# ngv-main.net
KiCad netlist of a schematic drawn in Altium Designer
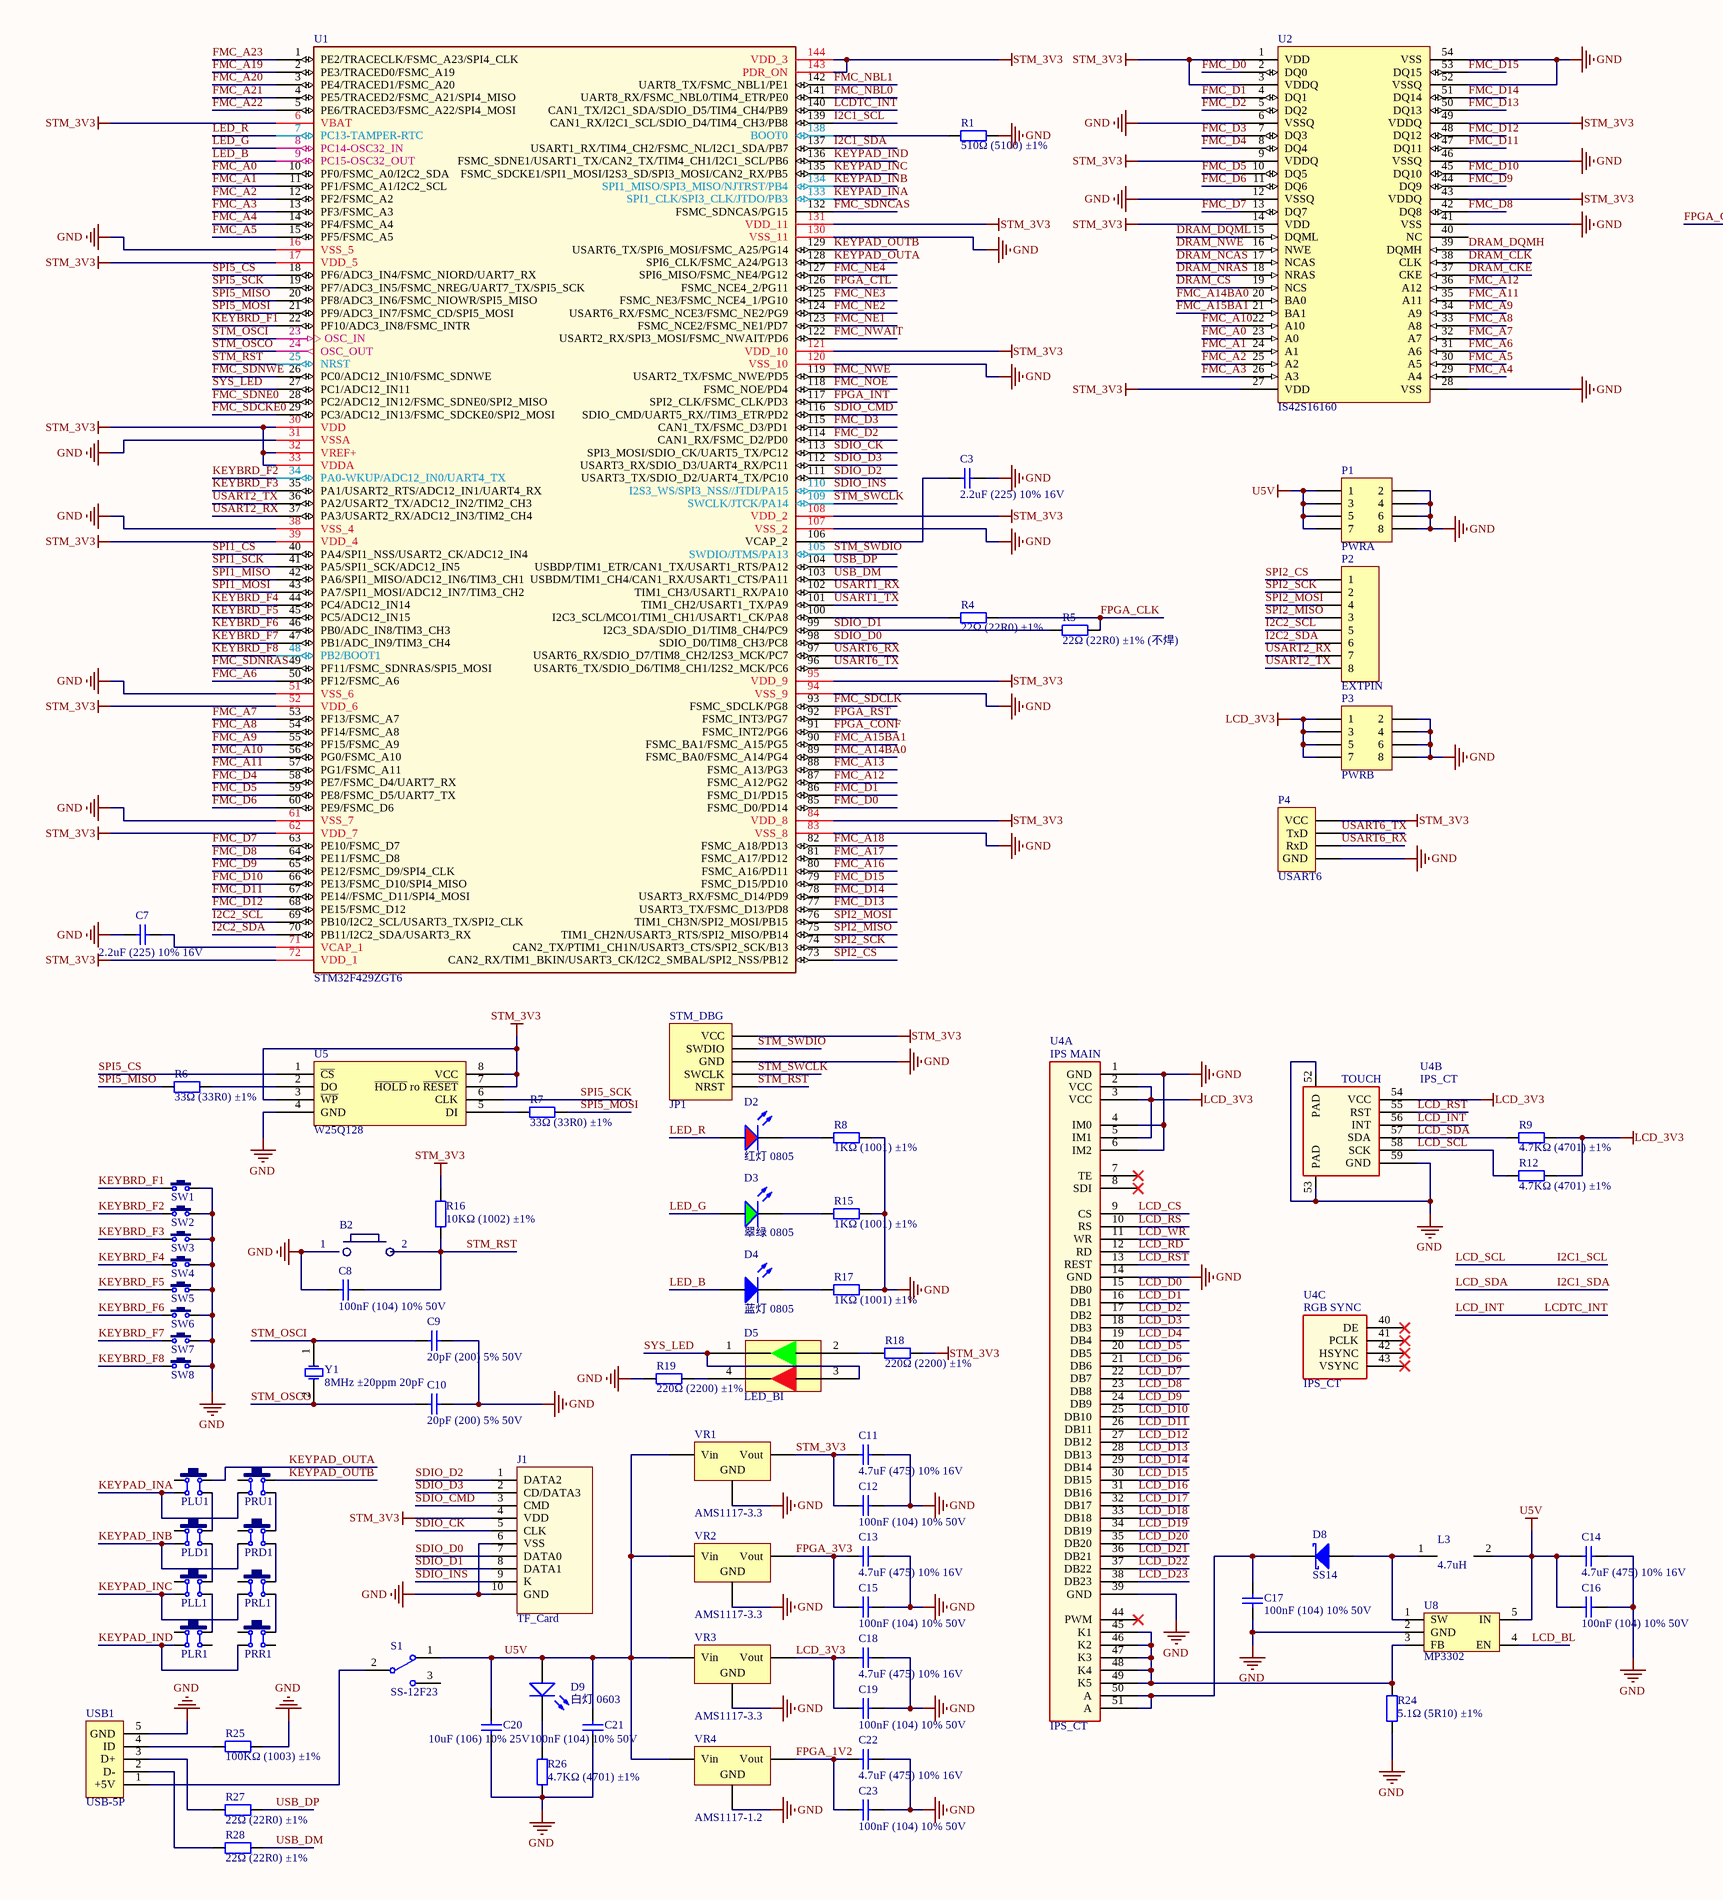
[diagram p0: ngv-main.SchDoc, left]
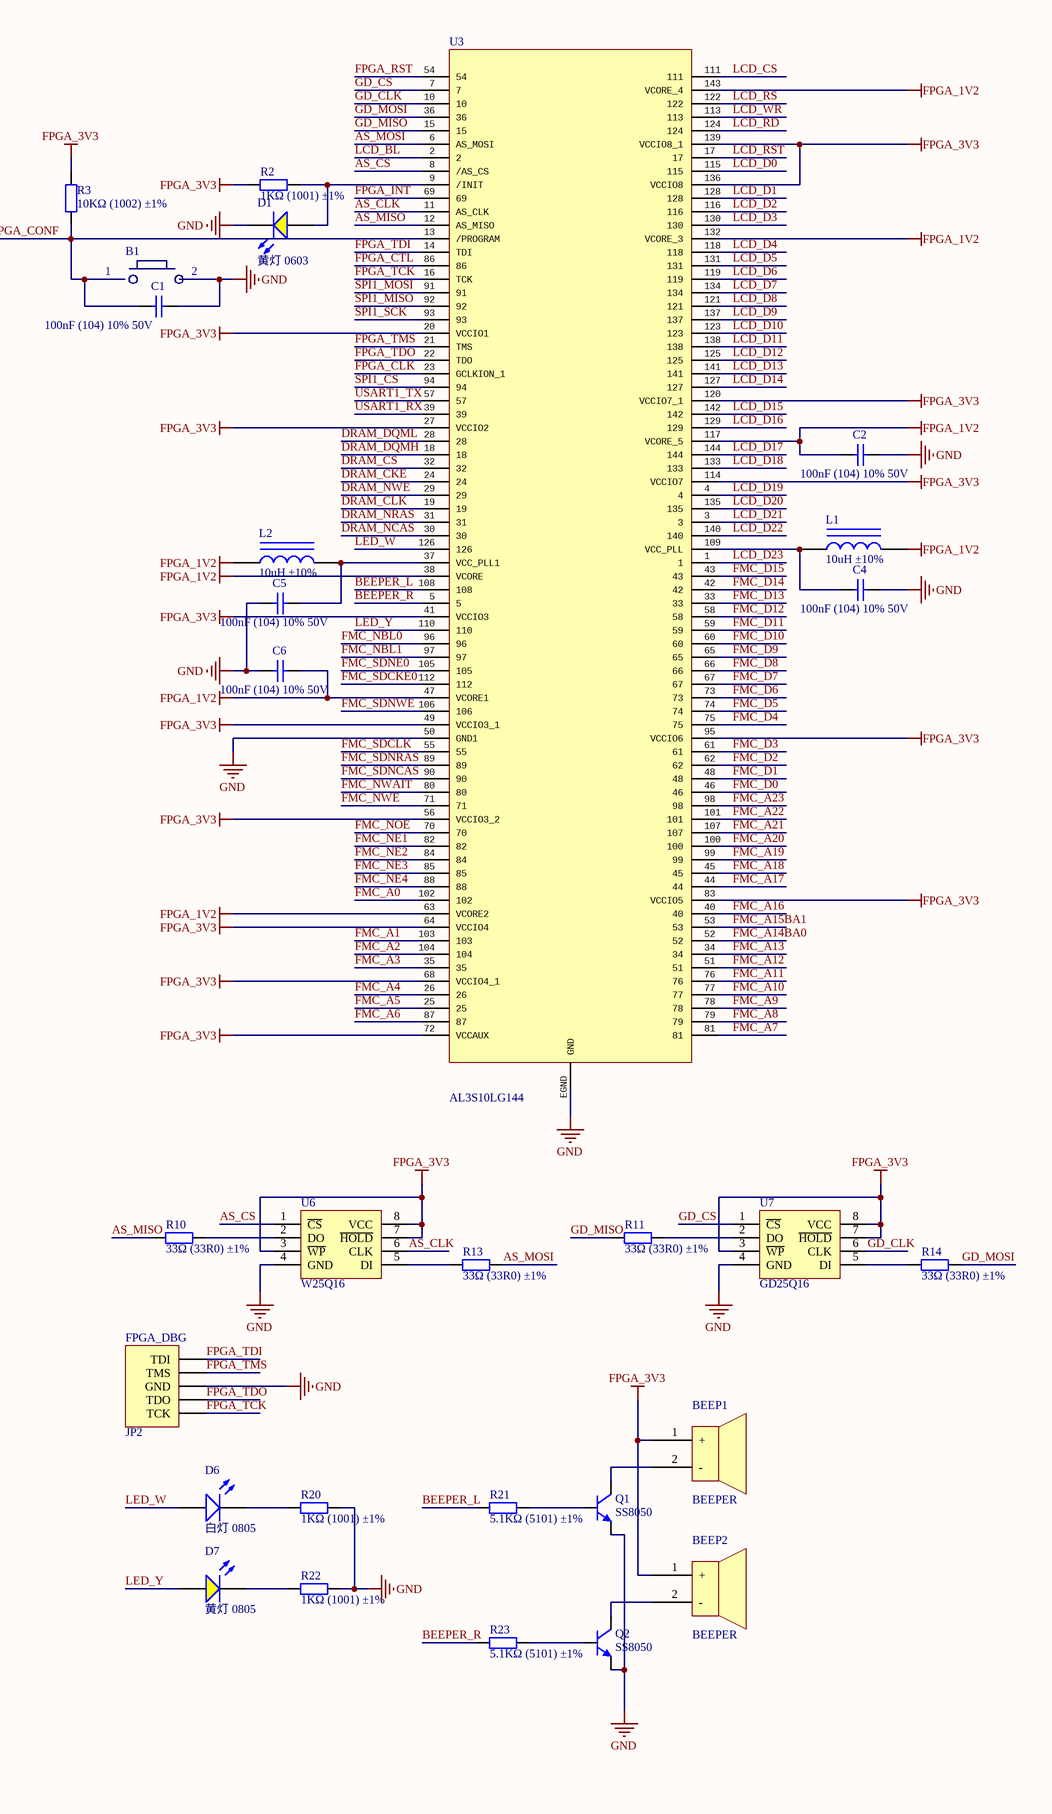
[diagram p1: ngv-main.SchDoc, right]

(export (version "E")
  (design (tool "Eeschema 10.0.6"))
  (components
    (comp (ref "B1")
      (value "B1")
      (footprint "MetalButton")
      (libsource (lib "MetalButton") (part "MetalButton"))
    )
    (comp (ref "B2")
      (value "B1")
      (footprint "MetalButton")
      (libsource (lib "MetalButton") (part "MetalButton"))
    )
    (comp (ref "BEEP1") (value "BEEPER") (footprint "BEEPER") (libsource (lib "ngv-main") (part "BEEPER")))
    (comp (ref "BEEP2") (value "BEEPER") (footprint "BEEPER") (libsource (lib "ngv-main") (part "BEEPER")))
    (comp (ref "C1")
      (value "100nF (104) 10% 50V")
      (footprint "0603_C")
      (description "贴片电容")
      (libsource (lib "Miscellaneous Devices LC") (part "0603 100nF (104) 10% 50V"))
    )
    (comp (ref "C2")
      (value "100nF (104) 10% 50V")
      (footprint "0603_C")
      (description "贴片电容")
      (libsource (lib "Miscellaneous Devices LC") (part "0603 100nF (104) 10% 50V"))
    )
    (comp (ref "C3")
      (value "2.2uF (225) 10% 16V")
      (footprint "0603_C")
      (description "贴片电容")
      (libsource (lib "Miscellaneous Devices LC") (part "0603 2.2uF (225) 10% 16V"))
    )
    (comp (ref "C4")
      (value "100nF (104) 10% 50V")
      (footprint "0603_C")
      (description "贴片电容")
      (libsource (lib "Miscellaneous Devices LC") (part "0603 100nF (104) 10% 50V"))
    )
    (comp (ref "C5")
      (value "100nF (104) 10% 50V")
      (footprint "0603_C")
      (description "贴片电容")
      (libsource (lib "Miscellaneous Devices LC") (part "0603 100nF (104) 10% 50V"))
    )
    (comp (ref "C6")
      (value "100nF (104) 10% 50V")
      (footprint "0603_C")
      (description "贴片电容")
      (libsource (lib "Miscellaneous Devices LC") (part "0603 100nF (104) 10% 50V"))
    )
    (comp (ref "C7")
      (value "2.2uF (225) 10% 16V")
      (footprint "0603_C")
      (description "贴片电容")
      (libsource (lib "Miscellaneous Devices LC") (part "0603 2.2uF (225) 10% 16V"))
    )
    (comp (ref "C8")
      (value "100nF (104) 10% 50V")
      (footprint "0603_C")
      (description "贴片电容")
      (libsource (lib "Miscellaneous Devices LC") (part "0603 100nF (104) 10% 50V"))
    )
    (comp (ref "C9")
      (value "20pF (200) 5% 50V")
      (footprint "0603_C")
      (description "贴片电容")
      (libsource (lib "Miscellaneous Devices LC") (part "0603 20pF (200) 5% 50V"))
    )
    (comp (ref "C10")
      (value "20pF (200) 5% 50V")
      (footprint "0603_C")
      (description "贴片电容")
      (libsource (lib "Miscellaneous Devices LC") (part "0603 20pF (200) 5% 50V"))
    )
    (comp (ref "C11")
      (value "4.7uF (475) 10% 16V")
      (footprint "0603_C")
      (description "贴片电容")
      (libsource (lib "Miscellaneous Devices LC") (part "0603 4.7uF (475) 10% 16V"))
    )
    (comp (ref "C12")
      (value "100nF (104) 10% 50V")
      (footprint "0603_C")
      (description "贴片电容")
      (libsource (lib "Miscellaneous Devices LC") (part "0603 100nF (104) 10% 50V"))
    )
    (comp (ref "C13")
      (value "4.7uF (475) 10% 16V")
      (footprint "0603_C")
      (description "贴片电容")
      (libsource (lib "Miscellaneous Devices LC") (part "0603 4.7uF (475) 10% 16V"))
    )
    (comp (ref "C14")
      (value "4.7uF (475) 10% 16V")
      (footprint "0603_C")
      (description "贴片电容")
      (libsource (lib "Miscellaneous Devices LC") (part "0603 4.7uF (475) 10% 16V"))
    )
    (comp (ref "C15")
      (value "100nF (104) 10% 50V")
      (footprint "0603_C")
      (description "贴片电容")
      (libsource (lib "Miscellaneous Devices LC") (part "0603 100nF (104) 10% 50V"))
    )
    (comp (ref "C16")
      (value "100nF (104) 10% 50V")
      (footprint "0603_C")
      (description "贴片电容")
      (libsource (lib "Miscellaneous Devices LC") (part "0603 100nF (104) 10% 50V"))
    )
    (comp (ref "C17")
      (value "100nF (104) 10% 50V")
      (footprint "0603_C")
      (description "贴片电容")
      (libsource (lib "Miscellaneous Devices LC") (part "0603 100nF (104) 10% 50V"))
    )
    (comp (ref "C18")
      (value "4.7uF (475) 10% 16V")
      (footprint "0603_C")
      (description "贴片电容")
      (libsource (lib "Miscellaneous Devices LC") (part "0603 4.7uF (475) 10% 16V"))
    )
    (comp (ref "C19")
      (value "100nF (104) 10% 50V")
      (footprint "0603_C")
      (description "贴片电容")
      (libsource (lib "Miscellaneous Devices LC") (part "0603 100nF (104) 10% 50V"))
    )
    (comp (ref "C20")
      (value "10uF (106) 10% 25V")
      (footprint "0805_C")
      (description "贴片电容")
      (libsource (lib "Miscellaneous Devices LC") (part "0805 10uF (106) 10% 25V"))
    )
    (comp (ref "C21")
      (value "100nF (104) 10% 50V")
      (footprint "0603_C")
      (description "贴片电容")
      (libsource (lib "Miscellaneous Devices LC") (part "0603 100nF (104) 10% 50V"))
    )
    (comp (ref "C22")
      (value "4.7uF (475) 10% 16V")
      (footprint "0603_C")
      (description "贴片电容")
      (libsource (lib "Miscellaneous Devices LC") (part "0603 4.7uF (475) 10% 16V"))
    )
    (comp (ref "C23")
      (value "100nF (104) 10% 50V")
      (footprint "0603_C")
      (description "贴片电容")
      (libsource (lib "Miscellaneous Devices LC") (part "0603 100nF (104) 10% 50V"))
    )
    (comp (ref "D1")
      (value "黄灯 0603")
      (footprint "0603_LED_S1")
      (description "发光二极管")
      (libsource (lib "Miscellaneous Devices LC") (part "0603 黄灯"))
    )
    (comp (ref "D2")
      (value "红灯 0805")
      (footprint "0805_LED_S1")
      (description "发光二极管")
      (libsource (lib "Miscellaneous Devices LC") (part "0805 红灯"))
    )
    (comp (ref "D3")
      (value "翠绿 0805")
      (footprint "0805_LED_S1")
      (description "发光二极管")
      (libsource (lib "Miscellaneous Devices LC") (part "0805 翠绿"))
    )
    (comp (ref "D4")
      (value "蓝灯 0805")
      (footprint "0805_LED_S1")
      (description "发光二极管")
      (libsource (lib "Miscellaneous Devices LC") (part "0805 蓝灯"))
    )
    (comp (ref "D5") (value "LED_BI") (footprint "LED_BI") (libsource (lib "ngv-main") (part "LED_BI")))
    (comp (ref "D6")
      (value "白灯 0805")
      (footprint "0805_LED_S1")
      (description "发光二极管")
      (libsource (lib "Miscellaneous Devices LC") (part "0805 白灯"))
    )
    (comp (ref "D7")
      (value "黄灯 0805")
      (footprint "0805_LED_S1")
      (description "发光二极管")
      (libsource (lib "Miscellaneous Devices LC") (part "0805 黄灯"))
    )
    (comp (ref "D8")
      (value "SS14")
      (footprint "SOD123")
      (fields (field (name "PUBLISHER") "Altium Limited"))
      (libsource (lib "Tiky_IPS_CT") (part "SS14"))
    )
    (comp (ref "D9")
      (value "白灯 0603")
      (footprint "0603_LED_S1")
      (description "发光二极管")
      (libsource (lib "Miscellaneous Devices LC") (part "0603 白灯"))
    )
    (comp (ref "J1")
      (value "TF_Card")
      (footprint "Micro SD")
      (description "TF卡座")
      (fields (field (name "版权归属") "源创客"))
      (libsource (lib "4.1   - 接口类") (part "TF_Card"))
    )
    (comp (ref "JP1")
      (value "STM_DBG")
      (footprint "XH2.54-WS-5P")
      (description "STM32")
      (fields (field (name "版权归属") "源创客"))
      (libsource (lib "ngv-main") (part "STM_HDR"))
    )
    (comp (ref "JP2")
      (value "FPGA_DBG")
      (footprint "XH2.54-WS-5P")
      (description "FPGA")
      (fields (field (name "版权归属") "源创客"))
      (libsource (lib "ngv-main") (part "FPGA_HDR"))
    )
    (comp (ref "L1")
      (value "10uH ±10%")
      (footprint "0603_L")
      (description "贴片电感")
      (libsource (lib "Miscellaneous Devices LC") (part "0603 10uH 10%"))
    )
    (comp (ref "L2")
      (value "10uH ±10%")
      (footprint "0603_L")
      (description "贴片电感")
      (libsource (lib "Miscellaneous Devices LC") (part "0603 10uH 10%"))
    )
    (comp (ref "L3") (value "4.7uH") (footprint "L453226") (libsource (lib "Tiky_IPS_CT") (part "4.7uH")))
    (comp (ref "P1")
      (value "PWRA")
      (footprint "HDR2X4")
      (description "Header, 4-Pin, Dual row")
      (fields (field (name "PUBLISHER") "Altium Limited"))
      (libsource (lib "Miscellaneous Connectors") (part "Header 4X2"))
    )
    (comp (ref "P2")
      (value "EXTPIN")
      (footprint "HDR1X8")
      (description "Header, 8-Pin")
      (fields (field (name "PUBLISHER") "Altium Limited"))
      (libsource (lib "Miscellaneous Connectors") (part "Header 8"))
    )
    (comp (ref "P3")
      (value "PWRB")
      (footprint "HDR2X4")
      (description "Header, 4-Pin, Dual row")
      (fields (field (name "PUBLISHER") "Altium Limited"))
      (libsource (lib "Miscellaneous Connectors") (part "Header 4X2"))
    )
    (comp (ref "P4")
      (value "USART6")
      (footprint "HDR1X4H")
      (description "Header, 4-Pin, Right Angle")
      (fields (field (name "PUBLISHER") "Altium Limited"))
      (libsource (lib "Miscellaneous Connectors") (part "Header 4H"))
    )
    (comp (ref "PLD1")
      (value "12x12x5")
      (footprint "TSW SMD-12*12*6")
      (description "贴片12x12轻触开关")
      (fields (field (name "版权归属") "源创客"))
      (libsource (lib "5.1   - 按键-开关") (part "TSW SMD-12x12"))
    )
    (comp (ref "PLL1")
      (value "12x12x5")
      (footprint "TSW SMD-12*12*6")
      (description "贴片12x12轻触开关")
      (fields (field (name "版权归属") "源创客"))
      (libsource (lib "5.1   - 按键-开关") (part "TSW SMD-12x12"))
    )
    (comp (ref "PLR1")
      (value "12x12x5")
      (footprint "TSW SMD-12*12*6")
      (description "贴片12x12轻触开关")
      (fields (field (name "版权归属") "源创客"))
      (libsource (lib "5.1   - 按键-开关") (part "TSW SMD-12x12"))
    )
    (comp (ref "PLU1")
      (value "12x12x5")
      (footprint "TSW SMD-12*12*6")
      (description "贴片12x12轻触开关")
      (fields (field (name "版权归属") "源创客"))
      (libsource (lib "5.1   - 按键-开关") (part "TSW SMD-12x12"))
    )
    (comp (ref "PRD1")
      (value "12x12x5")
      (footprint "TSW SMD-12*12*6")
      (description "贴片12x12轻触开关")
      (fields (field (name "版权归属") "源创客"))
      (libsource (lib "5.1   - 按键-开关") (part "TSW SMD-12x12"))
    )
    (comp (ref "PRL1")
      (value "12x12x5")
      (footprint "TSW SMD-12*12*6")
      (description "贴片12x12轻触开关")
      (fields (field (name "版权归属") "源创客"))
      (libsource (lib "5.1   - 按键-开关") (part "TSW SMD-12x12"))
    )
    (comp (ref "PRR1")
      (value "12x12x5")
      (footprint "TSW SMD-12*12*6")
      (description "贴片12x12轻触开关")
      (fields (field (name "版权归属") "源创客"))
      (libsource (lib "5.1   - 按键-开关") (part "TSW SMD-12x12"))
    )
    (comp (ref "PRU1")
      (value "12x12x5")
      (footprint "TSW SMD-12*12*6")
      (description "贴片12x12轻触开关")
      (fields (field (name "版权归属") "源创客"))
      (libsource (lib "5.1   - 按键-开关") (part "TSW SMD-12x12"))
    )
    (comp (ref "Q1")
      (value "SS8050")
      (footprint "SOT23-3M")
      (description "高频放大-NPN型")
      (fields (field (name "版权归属") "源创客"))
      (libsource (lib "6.2   - 三极管") (part "8050-SMD"))
    )
    (comp (ref "Q2")
      (value "SS8050")
      (footprint "SOT23-3M")
      (description "高频放大-NPN型")
      (fields (field (name "版权归属") "源创客"))
      (libsource (lib "6.2   - 三极管") (part "8050-SMD"))
    )
    (comp (ref "R1")
      (value "510Ω (5100) ±1%")
      (footprint "0603_R")
      (description "贴片电阻")
      (libsource (lib "Miscellaneous Devices LC") (part "0603 510Ω (5100) 1%"))
    )
    (comp (ref "R2")
      (value "1KΩ (1001) ±1%")
      (footprint "0603_R")
      (description "贴片电阻")
      (libsource (lib "Miscellaneous Devices LC") (part "0603 1KΩ (1001) 1%"))
    )
    (comp (ref "R3")
      (value "10KΩ (1002) ±1%")
      (footprint "0603_R")
      (description "贴片电阻")
      (libsource (lib "Miscellaneous Devices LC") (part "0603 10KΩ (1002) 1%"))
    )
    (comp (ref "R4")
      (value "22Ω (22R0) ±1%")
      (footprint "0805_R")
      (description "贴片电阻")
      (libsource (lib "Miscellaneous Devices LC") (part "0805 22Ω (22R0) 1%"))
    )
    (comp (ref "R5")
      (value "22Ω (22R0) ±1% (不焊)")
      (footprint "0805_R")
      (description "贴片电阻")
      (libsource (lib "Miscellaneous Devices LC") (part "0805 22Ω (22R0) 1%"))
    )
    (comp (ref "R6")
      (value "33Ω (33R0) ±1%")
      (footprint "0603_R")
      (description "贴片电阻")
      (libsource (lib "Miscellaneous Devices LC") (part "0603 33Ω (33R0) 1%"))
    )
    (comp (ref "R7")
      (value "33Ω (33R0) ±1%")
      (footprint "0603_R")
      (description "贴片电阻")
      (libsource (lib "Miscellaneous Devices LC") (part "0603 33Ω (33R0) 1%"))
    )
    (comp (ref "R8")
      (value "1KΩ (1001) ±1%")
      (footprint "0603_R")
      (description "贴片电阻")
      (libsource (lib "Miscellaneous Devices LC") (part "0603 1KΩ (1001) 1%"))
    )
    (comp (ref "R9")
      (value "4.7KΩ (4701) ±1%")
      (footprint "0603_R")
      (description "贴片电阻")
      (libsource (lib "Miscellaneous Devices LC") (part "0603 4.7KΩ (4701) 1%"))
    )
    (comp (ref "R10")
      (value "33Ω (33R0) ±1%")
      (footprint "0603_R")
      (description "贴片电阻")
      (libsource (lib "Miscellaneous Devices LC") (part "0603 33Ω (33R0) 1%"))
    )
    (comp (ref "R11")
      (value "33Ω (33R0) ±1%")
      (footprint "0603_R")
      (description "贴片电阻")
      (libsource (lib "Miscellaneous Devices LC") (part "0603 33Ω (33R0) 1%"))
    )
    (comp (ref "R12")
      (value "4.7KΩ (4701) ±1%")
      (footprint "0603_R")
      (description "贴片电阻")
      (libsource (lib "Miscellaneous Devices LC") (part "0603 4.7KΩ (4701) 1%"))
    )
    (comp (ref "R13")
      (value "33Ω (33R0) ±1%")
      (footprint "0603_R")
      (description "贴片电阻")
      (libsource (lib "Miscellaneous Devices LC") (part "0603 33Ω (33R0) 1%"))
    )
    (comp (ref "R14")
      (value "33Ω (33R0) ±1%")
      (footprint "0603_R")
      (description "贴片电阻")
      (libsource (lib "Miscellaneous Devices LC") (part "0603 33Ω (33R0) 1%"))
    )
    (comp (ref "R15")
      (value "1KΩ (1001) ±1%")
      (footprint "0603_R")
      (description "贴片电阻")
      (libsource (lib "Miscellaneous Devices LC") (part "0603 1KΩ (1001) 1%"))
    )
    (comp (ref "R16")
      (value "10KΩ (1002) ±1%")
      (footprint "0603_R")
      (description "贴片电阻")
      (libsource (lib "Miscellaneous Devices LC") (part "0603 10KΩ (1002) 1%"))
    )
    (comp (ref "R17")
      (value "1KΩ (1001) ±1%")
      (footprint "0603_R")
      (description "贴片电阻")
      (libsource (lib "Miscellaneous Devices LC") (part "0603 1KΩ (1001) 1%"))
    )
    (comp (ref "R18")
      (value "220Ω (2200) ±1%")
      (footprint "0402_R")
      (description "贴片电阻")
      (libsource (lib "Miscellaneous Devices LC") (part "0402 220Ω (2200) 1%"))
    )
    (comp (ref "R19")
      (value "220Ω (2200) ±1%")
      (footprint "0402_R")
      (description "贴片电阻")
      (libsource (lib "Miscellaneous Devices LC") (part "0402 220Ω (2200) 1%"))
    )
    (comp (ref "R20")
      (value "1KΩ (1001) ±1%")
      (footprint "0603_R")
      (description "贴片电阻")
      (libsource (lib "Miscellaneous Devices LC") (part "0603 1KΩ (1001) 1%"))
    )
    (comp (ref "R21")
      (value "5.1KΩ (5101) ±1%")
      (footprint "0603_R")
      (description "贴片电阻")
      (libsource (lib "Miscellaneous Devices LC") (part "0603 5.1KΩ (5101) 1%"))
    )
    (comp (ref "R22")
      (value "1KΩ (1001) ±1%")
      (footprint "0603_R")
      (description "贴片电阻")
      (libsource (lib "Miscellaneous Devices LC") (part "0603 1KΩ (1001) 1%"))
    )
    (comp (ref "R23")
      (value "5.1KΩ (5101) ±1%")
      (footprint "0603_R")
      (description "贴片电阻")
      (libsource (lib "Miscellaneous Devices LC") (part "0603 5.1KΩ (5101) 1%"))
    )
    (comp (ref "R24")
      (value "5.1Ω (5R10) ±1%")
      (footprint "0603_R")
      (description "贴片电阻")
      (libsource (lib "Miscellaneous Devices LC") (part "0603 5.1Ω (5R10) 1%"))
    )
    (comp (ref "R25")
      (value "100KΩ (1003) ±1%")
      (footprint "0603_R")
      (description "贴片电阻")
      (libsource (lib "Miscellaneous Devices LC") (part "0603 100KΩ (1003) 1%"))
    )
    (comp (ref "R26")
      (value "4.7KΩ (4701) ±1%")
      (footprint "0603_R")
      (description "贴片电阻")
      (libsource (lib "") (part "0603 4.7KΩ (4701) 1%_1"))
    )
    (comp (ref "R27")
      (value "22Ω (22R0) ±1%")
      (footprint "0603_R")
      (description "贴片电阻")
      (libsource (lib "Miscellaneous Devices LC") (part "0603 22Ω (22R0) 1%"))
    )
    (comp (ref "R28")
      (value "22Ω (22R0) ±1%")
      (footprint "0603_R")
      (description "贴片电阻")
      (libsource (lib "Miscellaneous Devices LC") (part "0603 22Ω (22R0) 1%"))
    )
    (comp (ref "S1")
      (value "SS-12F23")
      (footprint "SS-12F23")
      (description "1路波动开关")
      (fields (field (name "版权归属") "源创客"))
      (libsource (lib "5.1   - 按键-开关") (part "SSW-1P"))
    )
    (comp (ref "SW1")
      (value "3x6x5")
      (footprint "TSW SMD-3*6*4.3")
      (description "3x6轻触开关")
      (fields (field (name "版权归属") "源创客"))
      (libsource (lib "5.1   - 按键-开关") (part "TSW 3x6"))
    )
    (comp (ref "SW2")
      (value "3x6x5")
      (footprint "TSW SMD-3*6*4.3")
      (description "3x6轻触开关")
      (fields (field (name "版权归属") "源创客"))
      (libsource (lib "5.1   - 按键-开关") (part "TSW 3x6"))
    )
    (comp (ref "SW3")
      (value "3x6x5")
      (footprint "TSW SMD-3*6*4.3")
      (description "3x6轻触开关")
      (fields (field (name "版权归属") "源创客"))
      (libsource (lib "5.1   - 按键-开关") (part "TSW 3x6"))
    )
    (comp (ref "SW4")
      (value "3x6x5")
      (footprint "TSW SMD-3*6*4.3")
      (description "3x6轻触开关")
      (fields (field (name "版权归属") "源创客"))
      (libsource (lib "5.1   - 按键-开关") (part "TSW 3x6"))
    )
    (comp (ref "SW5")
      (value "3x6x5")
      (footprint "TSW SMD-3*6*4.3")
      (description "3x6轻触开关")
      (fields (field (name "版权归属") "源创客"))
      (libsource (lib "5.1   - 按键-开关") (part "TSW 3x6"))
    )
    (comp (ref "SW6")
      (value "3x6x5")
      (footprint "TSW SMD-3*6*4.3")
      (description "3x6轻触开关")
      (fields (field (name "版权归属") "源创客"))
      (libsource (lib "5.1   - 按键-开关") (part "TSW 3x6"))
    )
    (comp (ref "SW7")
      (value "3x6x5")
      (footprint "TSW SMD-3*6*4.3")
      (description "3x6轻触开关")
      (fields (field (name "版权归属") "源创客"))
      (libsource (lib "5.1   - 按键-开关") (part "TSW 3x6"))
    )
    (comp (ref "SW8")
      (value "3x6x5")
      (footprint "TSW SMD-3*6*4.3")
      (description "3x6轻触开关")
      (fields (field (name "版权归属") "源创客"))
      (libsource (lib "5.1   - 按键-开关") (part "TSW 3x6"))
    )
    (comp (ref "U1")
      (value "STM32F429ZGT6")
      (footprint "LQFP-144_20x20x05P")
      (description "ARM")
      (libsource (lib "Miscellaneous Devices LC") (part "STM32F429ZGT6"))
    )
    (comp (ref "U2")
      (value "IS42S16160")
      (footprint "TSOP54-II")
      (libsource (lib "ISSI_SDRAM") (part "IS42S16160"))
    )
    (comp (ref "U3")
      (value "AL3S10LG144")
      (footprint "AL_EQFP144")
      (libsource (lib "AL3S10LG144") (part "AL3S10LG144"))
    )
    (comp (ref "U4") (value "IPS_CT") (footprint "IPS_CT") (libsource (lib "Tiky_IPS_CT") (part "IPS_CT")))
    (comp (ref "U5")
      (value "W25Q128")
      (footprint "SOIC-8_208mil")
      (description "Flash ROM")
      (libsource (lib "Miscellaneous Devices LC") (part "W25Q128FVSIG_[C35101]"))
    )
    (comp (ref "U6")
      (value "W25Q16")
      (footprint "SOP8W_N")
      (description "外置Flash")
      (fields (field (name "版权归属") "源创客"))
      (libsource (lib "1.1   - IC芯片") (part "W25Qxx"))
    )
    (comp (ref "U7")
      (value "GD25Q16")
      (footprint "SOP8W_N")
      (description "外置Flash")
      (fields (field (name "版权归属") "源创客"))
      (libsource (lib "1.1   - IC芯片") (part "W25Qxx"))
    )
    (comp (ref "U8") (value "MP3302") (footprint "SOT23-5") (libsource (lib "Tiky_IPS_CT") (part "MP3302")))
    (comp (ref "USB1")
      (value "USB-5P")
      (footprint "USB-MICRO_D")
      (description "微型USB母座")
      (fields (field (name "版权归属") "源创客"))
      (libsource (lib "4.1   - 接口类") (part "USB-5P"))
    )
    (comp (ref "VR1")
      (value "AMS1117-3.3")
      (footprint "SOT-223")
      (description "低压差线性稳压(LDO)")
      (libsource (lib "Miscellaneous Devices LC") (part "SOT-223 AMS1117-3.3"))
    )
    (comp (ref "VR2")
      (value "AMS1117-3.3")
      (footprint "SOT-223")
      (description "低压差线性稳压(LDO)")
      (libsource (lib "Miscellaneous Devices LC") (part "SOT-223 AMS1117-3.3"))
    )
    (comp (ref "VR3")
      (value "AMS1117-3.3")
      (footprint "SOT-223")
      (description "低压差线性稳压(LDO)")
      (libsource (lib "Miscellaneous Devices LC") (part "SOT-223 AMS1117-3.3"))
    )
    (comp (ref "VR4")
      (value "AMS1117-1.2")
      (footprint "SOT-223")
      (description "低压差线性稳压(LDO)")
      (libsource (lib "Miscellaneous Devices LC") (part "SOT-223 AMS1117-3.3"))
    )
    (comp (ref "Y1")
      (value "8MHz ±20ppm 20pF")
      (footprint "SMD-5032_2P")
      (description "贴片晶振")
      (libsource (lib "Miscellaneous Devices LC") (part "SMD-5032_2P 8MHz 20ppm 20pF"))
    )
  )
  (nets
    (net (code "1") (name "/AS_CLK") (class "Default")
      (node (ref "U3") (pin "11") (pinfunction "AS_CLK_11") (pintype "passive"))
      (node (ref "U6") (pin "6") (pinfunction "CLK_6") (pintype "passive"))
    )
    (net (code "2") (name "/AS_CS") (class "Default")
      (node (ref "U3") (pin "8") (pinfunction "/AS_CS_8") (pintype "passive"))
      (node (ref "U6") (pin "1") (pinfunction "~{CS}_1") (pintype "passive"))
    )
    (net (code "3") (name "/AS_MISO") (class "Default")
      (node (ref "R10") (pin "1") (pinfunction "1_1") (pintype "passive"))
      (node (ref "U3") (pin "12") (pinfunction "AS_MISO_12") (pintype "passive"))
    )
    (net (code "4") (name "/AS_MOSI") (class "Default")
      (node (ref "R13") (pin "2") (pinfunction "2_2") (pintype "passive"))
      (node (ref "U3") (pin "6") (pinfunction "AS_MOSI_6") (pintype "passive"))
    )
    (net (code "5") (name "/BEEPER_L") (class "Default")
      (node (ref "R21") (pin "1") (pinfunction "1_1") (pintype "passive"))
      (node (ref "U3") (pin "108") (pinfunction "108_108") (pintype "passive"))
    )
    (net (code "6") (name "/BEEPER_R") (class "Default")
      (node (ref "R23") (pin "1") (pinfunction "1_1") (pintype "passive"))
      (node (ref "U3") (pin "5") (pinfunction "5_5") (pintype "passive"))
    )
    (net (code "7") (name "/DRAM_CKE") (class "Default")
      (node (ref "U2") (pin "37") (pinfunction "CKE_37") (pintype "input"))
      (node (ref "U3") (pin "24") (pinfunction "24_24") (pintype "passive"))
    )
    (net (code "8") (name "/DRAM_CLK") (class "Default")
      (node (ref "U2") (pin "38") (pinfunction "CLK_38") (pintype "input"))
      (node (ref "U3") (pin "19") (pinfunction "19_19") (pintype "passive"))
    )
    (net (code "9") (name "/DRAM_CS") (class "Default")
      (node (ref "U2") (pin "19") (pinfunction "NCS_19") (pintype "input"))
      (node (ref "U3") (pin "32") (pinfunction "32_32") (pintype "passive"))
    )
    (net (code "10") (name "/DRAM_DQMH") (class "Default")
      (node (ref "U2") (pin "39") (pinfunction "DQMH_39") (pintype "input"))
      (node (ref "U3") (pin "18") (pinfunction "18_18") (pintype "passive"))
    )
    (net (code "11") (name "/DRAM_DQML") (class "Default")
      (node (ref "U2") (pin "15") (pinfunction "DQML_15") (pintype "input"))
      (node (ref "U3") (pin "28") (pinfunction "28_28") (pintype "passive"))
    )
    (net (code "12") (name "/DRAM_NCAS") (class "Default")
      (node (ref "U2") (pin "17") (pinfunction "NCAS_17") (pintype "input"))
      (node (ref "U3") (pin "30") (pinfunction "30_30") (pintype "passive"))
    )
    (net (code "13") (name "/DRAM_NRAS") (class "Default")
      (node (ref "U2") (pin "18") (pinfunction "NRAS_18") (pintype "input"))
      (node (ref "U3") (pin "31") (pinfunction "31_31") (pintype "passive"))
    )
    (net (code "14") (name "/DRAM_NWE") (class "Default")
      (node (ref "U2") (pin "16") (pinfunction "NWE_16") (pintype "input"))
      (node (ref "U3") (pin "29") (pinfunction "29_29") (pintype "passive"))
    )
    (net (code "15") (name "/FMC_A0") (class "Default")
      (node (ref "U1") (pin "10") (pinfunction "PF0/FSMC_A0/I2C2_SDA_10") (pintype "bidirectional"))
      (node (ref "U2") (pin "23") (pinfunction "A0_23") (pintype "input"))
      (node (ref "U3") (pin "102") (pinfunction "102_102") (pintype "passive"))
    )
    (net (code "16") (name "/FMC_A1") (class "Default")
      (node (ref "U1") (pin "11") (pinfunction "PF1/FSMC_A1/I2C2_SCL_11") (pintype "bidirectional"))
      (node (ref "U2") (pin "24") (pinfunction "A1_24") (pintype "input"))
      (node (ref "U3") (pin "103") (pinfunction "103_103") (pintype "passive"))
    )
    (net (code "17") (name "/FMC_A2") (class "Default")
      (node (ref "U1") (pin "12") (pinfunction "PF2/FSMC_A2_12") (pintype "bidirectional"))
      (node (ref "U2") (pin "25") (pinfunction "A2_25") (pintype "input"))
      (node (ref "U3") (pin "104") (pinfunction "104_104") (pintype "passive"))
    )
    (net (code "18") (name "/FMC_A3") (class "Default")
      (node (ref "U1") (pin "13") (pinfunction "PF3/FSMC_A3_13") (pintype "bidirectional"))
      (node (ref "U2") (pin "26") (pinfunction "A3_26") (pintype "input"))
      (node (ref "U3") (pin "35") (pinfunction "35_35") (pintype "passive"))
    )
    (net (code "19") (name "/FMC_A4") (class "Default")
      (node (ref "U1") (pin "14") (pinfunction "PF4/FSMC_A4_14") (pintype "bidirectional"))
      (node (ref "U2") (pin "29") (pinfunction "A4_29") (pintype "input"))
      (node (ref "U3") (pin "26") (pinfunction "26_26") (pintype "passive"))
    )
    (net (code "20") (name "/FMC_A5") (class "Default")
      (node (ref "U1") (pin "15") (pinfunction "PF5/FSMC_A5_15") (pintype "bidirectional"))
      (node (ref "U2") (pin "30") (pinfunction "A5_30") (pintype "input"))
      (node (ref "U3") (pin "25") (pinfunction "25_25") (pintype "passive"))
    )
    (net (code "21") (name "/FMC_A6") (class "Default")
      (node (ref "U1") (pin "50") (pinfunction "PF12/FSMC_A6_50") (pintype "bidirectional"))
      (node (ref "U2") (pin "31") (pinfunction "A6_31") (pintype "input"))
      (node (ref "U3") (pin "87") (pinfunction "87_87") (pintype "passive"))
    )
    (net (code "22") (name "/FMC_A7") (class "Default")
      (node (ref "U1") (pin "53") (pinfunction "PF13/FSMC_A7_53") (pintype "bidirectional"))
      (node (ref "U2") (pin "32") (pinfunction "A7_32") (pintype "input"))
      (node (ref "U3") (pin "81") (pinfunction "81_81") (pintype "passive"))
    )
    (net (code "23") (name "/FMC_A8") (class "Default")
      (node (ref "U1") (pin "54") (pinfunction "PF14/FSMC_A8_54") (pintype "bidirectional"))
      (node (ref "U2") (pin "33") (pinfunction "A8_33") (pintype "input"))
      (node (ref "U3") (pin "79") (pinfunction "79_79") (pintype "passive"))
    )
    (net (code "24") (name "/FMC_A9") (class "Default")
      (node (ref "U1") (pin "55") (pinfunction "PF15/FSMC_A9_55") (pintype "bidirectional"))
      (node (ref "U2") (pin "34") (pinfunction "A9_34") (pintype "input"))
      (node (ref "U3") (pin "78") (pinfunction "78_78") (pintype "passive"))
    )
    (net (code "25") (name "/FMC_A10") (class "Default")
      (node (ref "U1") (pin "56") (pinfunction "PG0/FSMC_A10_56") (pintype "bidirectional"))
      (node (ref "U2") (pin "22") (pinfunction "A10_22") (pintype "input"))
      (node (ref "U3") (pin "77") (pinfunction "77_77") (pintype "passive"))
    )
    (net (code "26") (name "/FMC_A11") (class "Default")
      (node (ref "U1") (pin "57") (pinfunction "PG1/FSMC_A11_57") (pintype "bidirectional"))
      (node (ref "U2") (pin "35") (pinfunction "A11_35") (pintype "input"))
      (node (ref "U3") (pin "76") (pinfunction "76_76") (pintype "passive"))
    )
    (net (code "27") (name "/FMC_A12") (class "Default")
      (node (ref "U1") (pin "87") (pinfunction "FSMC_A12/PG2_87") (pintype "bidirectional"))
      (node (ref "U2") (pin "36") (pinfunction "A12_36") (pintype "input"))
      (node (ref "U3") (pin "51") (pinfunction "51_51") (pintype "passive"))
    )
    (net (code "28") (name "/FMC_A13") (class "Default")
      (node (ref "U1") (pin "88") (pinfunction "FSMC_A13/PG3_88") (pintype "bidirectional"))
      (node (ref "U3") (pin "34") (pinfunction "34_34") (pintype "passive"))
    )
    (net (code "29") (name "/FMC_A14BA0") (class "Default")
      (node (ref "U1") (pin "89") (pinfunction "FSMC_BA0/FSMC_A14/PG4_89") (pintype "bidirectional"))
      (node (ref "U2") (pin "20") (pinfunction "BA0_20") (pintype "input"))
      (node (ref "U3") (pin "52") (pinfunction "52_52") (pintype "passive"))
    )
    (net (code "30") (name "/FMC_A15BA1") (class "Default")
      (node (ref "U1") (pin "90") (pinfunction "FSMC_BA1/FSMC_A15/PG5_90") (pintype "bidirectional"))
      (node (ref "U2") (pin "21") (pinfunction "BA1_21") (pintype "input"))
      (node (ref "U3") (pin "53") (pinfunction "53_53") (pintype "passive"))
    )
    (net (code "31") (name "/FMC_A16") (class "Default")
      (node (ref "U1") (pin "80") (pinfunction "FSMC_A16/PD11_80") (pintype "bidirectional"))
      (node (ref "U3") (pin "40") (pinfunction "40_40") (pintype "passive"))
    )
    (net (code "32") (name "/FMC_A17") (class "Default")
      (node (ref "U1") (pin "81") (pinfunction "FSMC_A17/PD12_81") (pintype "bidirectional"))
      (node (ref "U3") (pin "44") (pinfunction "44_44") (pintype "passive"))
    )
    (net (code "33") (name "/FMC_A18") (class "Default")
      (node (ref "U1") (pin "82") (pinfunction "FSMC_A18/PD13_82") (pintype "bidirectional"))
      (node (ref "U3") (pin "45") (pinfunction "45_45") (pintype "passive"))
    )
    (net (code "34") (name "/FMC_A19") (class "Default")
      (node (ref "U1") (pin "2") (pinfunction "PE3/TRACED0/FSMC_A19_2") (pintype "bidirectional"))
      (node (ref "U3") (pin "99") (pinfunction "99_99") (pintype "passive"))
    )
    (net (code "35") (name "/FMC_A20") (class "Default")
      (node (ref "U1") (pin "3") (pinfunction "PE4/TRACED1/FSMC_A20_3") (pintype "bidirectional"))
      (node (ref "U3") (pin "100") (pinfunction "100_100") (pintype "passive"))
    )
    (net (code "36") (name "/FMC_A21") (class "Default")
      (node (ref "U1") (pin "4") (pinfunction "PE5/TRACED2/FSMC_A21/SPI4_MISO_4") (pintype "bidirectional"))
      (node (ref "U3") (pin "107") (pinfunction "107_107") (pintype "passive"))
    )
    (net (code "37") (name "/FMC_A22") (class "Default")
      (node (ref "U1") (pin "5") (pinfunction "PE6/TRACED3/FSMC_A22/SPI4_MOSI_5") (pintype "bidirectional"))
      (node (ref "U3") (pin "101") (pinfunction "101_101") (pintype "passive"))
    )
    (net (code "38") (name "/FMC_A23") (class "Default")
      (node (ref "U1") (pin "1") (pinfunction "PE2/TRACECLK/FSMC_A23/SPI4_CLK_1") (pintype "bidirectional"))
      (node (ref "U3") (pin "98") (pinfunction "98_98") (pintype "passive"))
    )
    (net (code "39") (name "/FMC_D0") (class "Default")
      (node (ref "U1") (pin "85") (pinfunction "FSMC_D0/PD14_85") (pintype "bidirectional"))
      (node (ref "U2") (pin "2") (pinfunction "DQ0_2") (pintype "bidirectional"))
      (node (ref "U3") (pin "46") (pinfunction "46_46") (pintype "passive"))
    )
    (net (code "40") (name "/FMC_D1") (class "Default")
      (node (ref "U1") (pin "86") (pinfunction "FSMC_D1/PD15_86") (pintype "bidirectional"))
      (node (ref "U2") (pin "4") (pinfunction "DQ1_4") (pintype "bidirectional"))
      (node (ref "U3") (pin "48") (pinfunction "48_48") (pintype "passive"))
    )
    (net (code "41") (name "/FMC_D2") (class "Default")
      (node (ref "U1") (pin "114") (pinfunction "CAN1_RX/FSMC_D2/PD0_114") (pintype "bidirectional"))
      (node (ref "U2") (pin "5") (pinfunction "DQ2_5") (pintype "bidirectional"))
      (node (ref "U3") (pin "62") (pinfunction "62_62") (pintype "passive"))
    )
    (net (code "42") (name "/FMC_D3") (class "Default")
      (node (ref "U1") (pin "115") (pinfunction "CAN1_TX/FSMC_D3/PD1_115") (pintype "bidirectional"))
      (node (ref "U2") (pin "7") (pinfunction "DQ3_7") (pintype "bidirectional"))
      (node (ref "U3") (pin "61") (pinfunction "61_61") (pintype "passive"))
    )
    (net (code "43") (name "/FMC_D4") (class "Default")
      (node (ref "U1") (pin "58") (pinfunction "PE7/FSMC_D4/UART7_RX_58") (pintype "bidirectional"))
      (node (ref "U2") (pin "8") (pinfunction "DQ4_8") (pintype "bidirectional"))
      (node (ref "U3") (pin "75") (pinfunction "75_75") (pintype "passive"))
    )
    (net (code "44") (name "/FMC_D5") (class "Default")
      (node (ref "U1") (pin "59") (pinfunction "PE8/FSMC_D5/UART7_TX_59") (pintype "bidirectional"))
      (node (ref "U2") (pin "10") (pinfunction "DQ5_10") (pintype "bidirectional"))
      (node (ref "U3") (pin "74") (pinfunction "74_74") (pintype "passive"))
    )
    (net (code "45") (name "/FMC_D6") (class "Default")
      (node (ref "U1") (pin "60") (pinfunction "PE9/FSMC_D6_60") (pintype "bidirectional"))
      (node (ref "U2") (pin "11") (pinfunction "DQ6_11") (pintype "bidirectional"))
      (node (ref "U3") (pin "73") (pinfunction "73_73") (pintype "passive"))
    )
    (net (code "46") (name "/FMC_D7") (class "Default")
      (node (ref "U1") (pin "63") (pinfunction "PE10/FSMC_D7_63") (pintype "bidirectional"))
      (node (ref "U2") (pin "13") (pinfunction "DQ7_13") (pintype "bidirectional"))
      (node (ref "U3") (pin "67") (pinfunction "67_67") (pintype "passive"))
    )
    (net (code "47") (name "/FMC_D8") (class "Default")
      (node (ref "U1") (pin "64") (pinfunction "PE11/FSMC_D8_64") (pintype "bidirectional"))
      (node (ref "U2") (pin "42") (pinfunction "DQ8_42") (pintype "bidirectional"))
      (node (ref "U3") (pin "66") (pinfunction "66_66") (pintype "passive"))
    )
    (net (code "48") (name "/FMC_D9") (class "Default")
      (node (ref "U1") (pin "65") (pinfunction "PE12/FSMC_D9/SPI4_CLK_65") (pintype "bidirectional"))
      (node (ref "U2") (pin "44") (pinfunction "DQ9_44") (pintype "bidirectional"))
      (node (ref "U3") (pin "65") (pinfunction "65_65") (pintype "passive"))
    )
    (net (code "49") (name "/FMC_D10") (class "Default")
      (node (ref "U1") (pin "66") (pinfunction "PE13/FSMC_D10/SPI4_MISO_66") (pintype "bidirectional"))
      (node (ref "U2") (pin "45") (pinfunction "DQ10_45") (pintype "bidirectional"))
      (node (ref "U3") (pin "60") (pinfunction "60_60") (pintype "passive"))
    )
    (net (code "50") (name "/FMC_D11") (class "Default")
      (node (ref "U1") (pin "67") (pinfunction "PE14//FSMC_D11/SPI4_MOSI_67") (pintype "bidirectional"))
      (node (ref "U2") (pin "47") (pinfunction "DQ11_47") (pintype "bidirectional"))
      (node (ref "U3") (pin "59") (pinfunction "59_59") (pintype "passive"))
    )
    (net (code "51") (name "/FMC_D12") (class "Default")
      (node (ref "U1") (pin "68") (pinfunction "PE15/FSMC_D12_68") (pintype "bidirectional"))
      (node (ref "U2") (pin "48") (pinfunction "DQ12_48") (pintype "bidirectional"))
      (node (ref "U3") (pin "58") (pinfunction "58_58") (pintype "passive"))
    )
    (net (code "52") (name "/FMC_D13") (class "Default")
      (node (ref "U1") (pin "77") (pinfunction "USART3_TX/FSMC_D13/PD8_77") (pintype "bidirectional"))
      (node (ref "U2") (pin "50") (pinfunction "DQ13_50") (pintype "bidirectional"))
      (node (ref "U3") (pin "33") (pinfunction "33_33") (pintype "passive"))
    )
    (net (code "53") (name "/FMC_D14") (class "Default")
      (node (ref "U1") (pin "78") (pinfunction "USART3_RX/FSMC_D14/PD9_78") (pintype "bidirectional"))
      (node (ref "U2") (pin "51") (pinfunction "DQ14_51") (pintype "bidirectional"))
      (node (ref "U3") (pin "42") (pinfunction "42_42") (pintype "passive"))
    )
    (net (code "54") (name "/FMC_D15") (class "Default")
      (node (ref "U1") (pin "79") (pinfunction "FSMC_D15/PD10_79") (pintype "bidirectional"))
      (node (ref "U2") (pin "53") (pinfunction "DQ15_53") (pintype "bidirectional"))
      (node (ref "U3") (pin "43") (pinfunction "43_43") (pintype "passive"))
    )
    (net (code "55") (name "/FMC_NBL0") (class "Default")
      (node (ref "U1") (pin "141") (pinfunction "UART8_RX/FSMC_NBL0/TIM4_ETR/PE0_141") (pintype "bidirectional"))
      (node (ref "U3") (pin "96") (pinfunction "96_96") (pintype "passive"))
    )
    (net (code "56") (name "/FMC_NBL1") (class "Default")
      (node (ref "U1") (pin "142") (pinfunction "UART8_TX/FSMC_NBL1/PE1_142") (pintype "bidirectional"))
      (node (ref "U3") (pin "97") (pinfunction "97_97") (pintype "passive"))
    )
    (net (code "57") (name "/FMC_NE1") (class "Default")
      (node (ref "U1") (pin "123") (pinfunction "FSMC_NCE2/FSMC_NE1/PD7_123") (pintype "bidirectional"))
      (node (ref "U3") (pin "82") (pinfunction "82_82") (pintype "passive"))
    )
    (net (code "58") (name "/FMC_NE2") (class "Default")
      (node (ref "U1") (pin "124") (pinfunction "USART6_RX/FSMC_NCE3/FSMC_NE2/PG9_124") (pintype "bidirectional"))
      (node (ref "U3") (pin "84") (pinfunction "84_84") (pintype "passive"))
    )
    (net (code "59") (name "/FMC_NE3") (class "Default")
      (node (ref "U1") (pin "125") (pinfunction "FSMC_NE3/FSMC_NCE4_1/PG10_125") (pintype "bidirectional"))
      (node (ref "U3") (pin "85") (pinfunction "85_85") (pintype "passive"))
    )
    (net (code "60") (name "/FMC_NE4") (class "Default")
      (node (ref "U1") (pin "127") (pinfunction "SPI6_MISO/FSMC_NE4/PG12_127") (pintype "bidirectional"))
      (node (ref "U3") (pin "88") (pinfunction "88_88") (pintype "passive"))
    )
    (net (code "61") (name "/FMC_NOE") (class "Default")
      (node (ref "U1") (pin "118") (pinfunction "FSMC_NOE/PD4_118") (pintype "bidirectional"))
      (node (ref "U3") (pin "70") (pinfunction "70_70") (pintype "passive"))
    )
    (net (code "62") (name "/FMC_NWAIT") (class "Default")
      (node (ref "U1") (pin "122") (pinfunction "USART2_RX/SPI3_MOSI/FSMC_NWAIT/PD6_122") (pintype "bidirectional"))
      (node (ref "U3") (pin "80") (pinfunction "80_80") (pintype "passive"))
    )
    (net (code "63") (name "/FMC_NWE") (class "Default")
      (node (ref "U1") (pin "119") (pinfunction "USART2_TX/FSMC_NWE/PD5_119") (pintype "bidirectional"))
      (node (ref "U3") (pin "71") (pinfunction "71_71") (pintype "passive"))
    )
    (net (code "64") (name "/FMC_SDCKE0") (class "Default")
      (node (ref "U1") (pin "29") (pinfunction "PC3/ADC12_IN13/FSMC_SDCKE0/SPI2_MOSI_29") (pintype "bidirectional"))
      (node (ref "U3") (pin "112") (pinfunction "112_112") (pintype "passive"))
    )
    (net (code "65") (name "/FMC_SDCLK") (class "Default")
      (node (ref "U1") (pin "93") (pinfunction "FSMC_SDCLK/PG8_93") (pintype "bidirectional"))
      (node (ref "U3") (pin "55") (pinfunction "55_55") (pintype "passive"))
    )
    (net (code "66") (name "/FMC_SDNCAS") (class "Default")
      (node (ref "U1") (pin "132") (pinfunction "FSMC_SDNCAS/PG15_132") (pintype "passive"))
      (node (ref "U3") (pin "90") (pinfunction "90_90") (pintype "passive"))
    )
    (net (code "67") (name "/FMC_SDNE0") (class "Default")
      (node (ref "U1") (pin "28") (pinfunction "PC2/ADC12_IN12/FSMC_SDNE0/SPI2_MISO_28") (pintype "bidirectional"))
      (node (ref "U3") (pin "105") (pinfunction "105_105") (pintype "passive"))
    )
    (net (code "68") (name "/FMC_SDNRAS") (class "Default")
      (node (ref "U1") (pin "49") (pinfunction "PF11/FSMC_SDNRAS/SPI5_MOSI_49") (pintype "bidirectional"))
      (node (ref "U3") (pin "89") (pinfunction "89_89") (pintype "passive"))
    )
    (net (code "69") (name "/FMC_SDNWE") (class "Default")
      (node (ref "U1") (pin "26") (pinfunction "PC0/ADC12_IN10/FSMC_SDNWE_26") (pintype "bidirectional"))
      (node (ref "U3") (pin "106") (pinfunction "106_106") (pintype "passive"))
    )
    (net (code "70") (name "/FPGA_CLK") (class "Default")
      (node (ref "R4") (pin "2") (pinfunction "2_2") (pintype "passive"))
      (node (ref "R5") (pin "2") (pinfunction "2_2") (pintype "passive"))
      (node (ref "U3") (pin "23") (pinfunction "GCLKION_1_23") (pintype "passive"))
    )
    (net (code "71") (name "/FPGA_CONF") (class "Default")
      (node (ref "B1") (pin "1") (pinfunction "1_1") (pintype "passive"))
      (node (ref "C1") (pin "1") (pinfunction "1_1") (pintype "passive"))
      (node (ref "R3") (pin "1") (pinfunction "1_1") (pintype "passive"))
      (node (ref "U1") (pin "91") (pinfunction "FSMC_INT2/PG6_91") (pintype "bidirectional"))
      (node (ref "U3") (pin "13") (pinfunction "/PROGRAM_13") (pintype "passive"))
    )
    (net (code "72") (name "/FPGA_CTL") (class "Default")
      (node (ref "U1") (pin "126") (pinfunction "FSMC_NCE4_2/PG11_126") (pintype "bidirectional"))
      (node (ref "U3") (pin "86") (pinfunction "86_86") (pintype "passive"))
    )
    (net (code "73") (name "/FPGA_INT") (class "Default")
      (node (ref "U1") (pin "117") (pinfunction "SPI2_CLK/FSMC_CLK/PD3_117") (pintype "bidirectional"))
      (node (ref "U3") (pin "69") (pinfunction "69_69") (pintype "passive"))
    )
    (net (code "74") (name "/FPGA_RST") (class "Default")
      (node (ref "U1") (pin "92") (pinfunction "FSMC_INT3/PG7_92") (pintype "bidirectional"))
      (node (ref "U3") (pin "54") (pinfunction "54_54") (pintype "passive"))
    )
    (net (code "75") (name "/FPGA_TCK") (class "Default")
      (node (ref "JP2") (pin "1") (pinfunction "TCK_1") (pintype "passive"))
      (node (ref "U3") (pin "16") (pinfunction "TCK_16") (pintype "passive"))
    )
    (net (code "76") (name "/FPGA_TDI") (class "Default")
      (node (ref "JP2") (pin "5") (pinfunction "TDI_5") (pintype "passive"))
      (node (ref "U3") (pin "14") (pinfunction "TDI_14") (pintype "passive"))
    )
    (net (code "77") (name "/FPGA_TDO") (class "Default")
      (node (ref "JP2") (pin "2") (pinfunction "TDO_2") (pintype "passive"))
      (node (ref "U3") (pin "22") (pinfunction "TDO_22") (pintype "passive"))
    )
    (net (code "78") (name "/FPGA_TMS") (class "Default")
      (node (ref "JP2") (pin "4") (pinfunction "TMS_4") (pintype "passive"))
      (node (ref "U3") (pin "21") (pinfunction "TMS_21") (pintype "passive"))
    )
    (net (code "79") (name "/GD_CLK") (class "Default")
      (node (ref "U3") (pin "10") (pinfunction "10_10") (pintype "passive"))
      (node (ref "U7") (pin "6") (pinfunction "CLK_6") (pintype "passive"))
    )
    (net (code "80") (name "/GD_CS") (class "Default")
      (node (ref "U3") (pin "7") (pinfunction "7_7") (pintype "passive"))
      (node (ref "U7") (pin "1") (pinfunction "~{CS}_1") (pintype "passive"))
    )
    (net (code "81") (name "/GD_MISO") (class "Default")
      (node (ref "R11") (pin "1") (pinfunction "1_1") (pintype "passive"))
      (node (ref "U3") (pin "15") (pinfunction "15_15") (pintype "passive"))
    )
    (net (code "82") (name "/GD_MOSI") (class "Default")
      (node (ref "R14") (pin "2") (pinfunction "2_2") (pintype "passive"))
      (node (ref "U3") (pin "36") (pinfunction "36_36") (pintype "passive"))
    )
    (net (code "83") (name "/I2C1_SCL") (class "Default")
      (node (ref "R12") (pin "1") (pinfunction "1_1") (pintype "passive"))
      (node (ref "U1") (pin "139") (pinfunction "CAN1_RX/I2C1_SCL/SDIO_D4/TIM4_CH3/PB8_139") (pintype "bidirectional"))
      (node (ref "U4") (pin "58") (pinfunction "SCK_58") (pintype "passive"))
    )
    (net (code "84") (name "/I2C1_SDA") (class "Default")
      (node (ref "R9") (pin "1") (pinfunction "1_1") (pintype "passive"))
      (node (ref "U1") (pin "137") (pinfunction "USART1_RX/TIM4_CH2/FSMC_NL/I2C1_SDA/PB7_137") (pintype "bidirectional"))
      (node (ref "U4") (pin "57") (pinfunction "SDA_57") (pintype "passive"))
    )
    (net (code "85") (name "/I2C2_SCL") (class "Default")
      (node (ref "P2") (pin "5") (pinfunction "5_5") (pintype "passive"))
      (node (ref "U1") (pin "69") (pinfunction "PB10/I2C2_SCL/USART3_TX/SPI2_CLK_69") (pintype "bidirectional"))
    )
    (net (code "86") (name "/I2C2_SDA") (class "Default")
      (node (ref "P2") (pin "6") (pinfunction "6_6") (pintype "passive"))
      (node (ref "U1") (pin "70") (pinfunction "PB11/I2C2_SDA/USART3_RX_70") (pintype "bidirectional"))
    )
    (net (code "87") (name "/KEYBRD_F1") (class "Default")
      (node (ref "SW1") (pin "1") (pinfunction "1_1") (pintype "passive"))
      (node (ref "U1") (pin "22") (pinfunction "PF10/ADC3_IN8/FSMC_INTR_22") (pintype "bidirectional"))
    )
    (net (code "88") (name "/KEYBRD_F2") (class "Default")
      (node (ref "SW2") (pin "1") (pinfunction "1_1") (pintype "passive"))
      (node (ref "U1") (pin "34") (pinfunction "PA0-WKUP/ADC12_IN0/UART4_TX_34") (pintype "bidirectional"))
    )
    (net (code "89") (name "/KEYBRD_F3") (class "Default")
      (node (ref "SW3") (pin "1") (pinfunction "1_1") (pintype "passive"))
      (node (ref "U1") (pin "35") (pinfunction "PA1/USART2_RTS/ADC12_IN1/UART4_RX_35") (pintype "bidirectional"))
    )
    (net (code "90") (name "/KEYBRD_F4") (class "Default")
      (node (ref "SW4") (pin "1") (pinfunction "1_1") (pintype "passive"))
      (node (ref "U1") (pin "44") (pinfunction "PC4/ADC12_IN14_44") (pintype "bidirectional"))
    )
    (net (code "91") (name "/KEYBRD_F5") (class "Default")
      (node (ref "SW5") (pin "1") (pinfunction "1_1") (pintype "passive"))
      (node (ref "U1") (pin "45") (pinfunction "PC5/ADC12_IN15_45") (pintype "bidirectional"))
    )
    (net (code "92") (name "/KEYBRD_F6") (class "Default")
      (node (ref "SW6") (pin "1") (pinfunction "1_1") (pintype "passive"))
      (node (ref "U1") (pin "46") (pinfunction "PB0/ADC_IN8/TIM3_CH3_46") (pintype "bidirectional"))
    )
    (net (code "93") (name "/KEYBRD_F7") (class "Default")
      (node (ref "SW7") (pin "1") (pinfunction "1_1") (pintype "passive"))
      (node (ref "U1") (pin "47") (pinfunction "PB1/ADC_IN9/TIM3_CH4_47") (pintype "bidirectional"))
    )
    (net (code "94") (name "/KEYBRD_F8") (class "Default")
      (node (ref "SW8") (pin "1") (pinfunction "1_1") (pintype "passive"))
      (node (ref "U1") (pin "48") (pinfunction "PB2/BOOT1_48") (pintype "bidirectional"))
    )
    (net (code "95") (name "/KEYPAD_INA") (class "Default")
      (node (ref "PLU1") (pin "4") (pinfunction "4_4") (pintype "passive"))
      (node (ref "PRU1") (pin "4") (pinfunction "4_4") (pintype "passive"))
      (node (ref "U1") (pin "133") (pinfunction "SPI1_CLK/SPI3_CLK/JTDO/PB3_133") (pintype "bidirectional"))
    )
    (net (code "96") (name "/KEYPAD_INB") (class "Default")
      (node (ref "PLD1") (pin "4") (pinfunction "4_4") (pintype "passive"))
      (node (ref "PRD1") (pin "4") (pinfunction "4_4") (pintype "passive"))
      (node (ref "U1") (pin "134") (pinfunction "SPI1_MISO/SPI3_MISO/NJTRST/PB4_134") (pintype "bidirectional"))
    )
    (net (code "97") (name "/KEYPAD_INC") (class "Default")
      (node (ref "PLL1") (pin "4") (pinfunction "4_4") (pintype "passive"))
      (node (ref "PRL1") (pin "4") (pinfunction "4_4") (pintype "passive"))
      (node (ref "U1") (pin "135") (pinfunction "FSMC_SDCKE1/SPI1_MOSI/I2S3_SD/SPI3_MOSI/CAN2_RX/PB5_135") (pintype "bidirectional"))
    )
    (net (code "98") (name "/KEYPAD_IND") (class "Default")
      (node (ref "PLR1") (pin "4") (pinfunction "4_4") (pintype "passive"))
      (node (ref "PRR1") (pin "4") (pinfunction "4_4") (pintype "passive"))
      (node (ref "U1") (pin "136") (pinfunction "FSMC_SDNE1/USART1_TX/CAN2_TX/TIM4_CH1/I2C1_SCL/PB6_136") (pintype "bidirectional"))
    )
    (net (code "99") (name "/KEYPAD_OUTA") (class "Default")
      (node (ref "PLU1") (pin "2") (pinfunction "2_2") (pintype "passive"))
      (node (ref "U1") (pin "128") (pinfunction "SPI6_CLK/FSMC_A24/PG13_128") (pintype "bidirectional"))
    )
    (net (code "100") (name "/KEYPAD_OUTB") (class "Default")
      (node (ref "PRU1") (pin "2") (pinfunction "2_2") (pintype "passive"))
      (node (ref "U1") (pin "129") (pinfunction "USART6_TX/SPI6_MOSI/FSMC_A25/PG14_129") (pintype "bidirectional"))
    )
    (net (code "101") (name "/LCDTC_INT") (class "Default")
      (node (ref "U1") (pin "140") (pinfunction "CAN1_TX/I2C1_SDA/SDIO_D5/TIM4_CH4/PB9_140") (pintype "bidirectional"))
      (node (ref "U4") (pin "56") (pinfunction "INT_56") (pintype "passive"))
    )
    (net (code "102") (name "/LCD_BL") (class "Default")
      (node (ref "U3") (pin "2") (pinfunction "2_2") (pintype "passive"))
      (node (ref "U8") (pin "4") (pinfunction "EN_4") (pintype "passive"))
    )
    (net (code "103") (name "/LCD_CS") (class "Default")
      (node (ref "U3") (pin "111") (pinfunction "111_111") (pintype "passive"))
      (node (ref "U4") (pin "9") (pinfunction "CS_9") (pintype "passive"))
    )
    (net (code "104") (name "/LCD_D0") (class "Default")
      (node (ref "U3") (pin "115") (pinfunction "115_115") (pintype "passive"))
      (node (ref "U4") (pin "15") (pinfunction "DB0_15") (pintype "passive"))
    )
    (net (code "105") (name "/LCD_D1") (class "Default")
      (node (ref "U3") (pin "128") (pinfunction "128_128") (pintype "passive"))
      (node (ref "U4") (pin "16") (pinfunction "DB1_16") (pintype "passive"))
    )
    (net (code "106") (name "/LCD_D2") (class "Default")
      (node (ref "U3") (pin "116") (pinfunction "116_116") (pintype "passive"))
      (node (ref "U4") (pin "17") (pinfunction "DB2_17") (pintype "passive"))
    )
    (net (code "107") (name "/LCD_D3") (class "Default")
      (node (ref "U3") (pin "130") (pinfunction "130_130") (pintype "passive"))
      (node (ref "U4") (pin "18") (pinfunction "DB3_18") (pintype "passive"))
    )
    (net (code "108") (name "/LCD_D4") (class "Default")
      (node (ref "U3") (pin "118") (pinfunction "118_118") (pintype "passive"))
      (node (ref "U4") (pin "19") (pinfunction "DB4_19") (pintype "passive"))
    )
    (net (code "109") (name "/LCD_D5") (class "Default")
      (node (ref "U3") (pin "131") (pinfunction "131_131") (pintype "passive"))
      (node (ref "U4") (pin "20") (pinfunction "DB5_20") (pintype "passive"))
    )
    (net (code "110") (name "/LCD_D6") (class "Default")
      (node (ref "U3") (pin "119") (pinfunction "119_119") (pintype "passive"))
      (node (ref "U4") (pin "21") (pinfunction "DB6_21") (pintype "passive"))
    )
    (net (code "111") (name "/LCD_D7") (class "Default")
      (node (ref "U3") (pin "134") (pinfunction "134_134") (pintype "passive"))
      (node (ref "U4") (pin "22") (pinfunction "DB7_22") (pintype "passive"))
    )
    (net (code "112") (name "/LCD_D8") (class "Default")
      (node (ref "U3") (pin "121") (pinfunction "121_121") (pintype "passive"))
      (node (ref "U4") (pin "23") (pinfunction "DB8_23") (pintype "passive"))
    )
    (net (code "113") (name "/LCD_D9") (class "Default")
      (node (ref "U3") (pin "137") (pinfunction "137_137") (pintype "passive"))
      (node (ref "U4") (pin "24") (pinfunction "DB9_24") (pintype "passive"))
    )
    (net (code "114") (name "/LCD_D10") (class "Default")
      (node (ref "U3") (pin "123") (pinfunction "123_123") (pintype "passive"))
      (node (ref "U4") (pin "25") (pinfunction "DB10_25") (pintype "passive"))
    )
    (net (code "115") (name "/LCD_D11") (class "Default")
      (node (ref "U3") (pin "138") (pinfunction "138_138") (pintype "passive"))
      (node (ref "U4") (pin "26") (pinfunction "DB11_26") (pintype "passive"))
    )
    (net (code "116") (name "/LCD_D12") (class "Default")
      (node (ref "U3") (pin "125") (pinfunction "125_125") (pintype "passive"))
      (node (ref "U4") (pin "27") (pinfunction "DB12_27") (pintype "passive"))
    )
    (net (code "117") (name "/LCD_D13") (class "Default")
      (node (ref "U3") (pin "141") (pinfunction "141_141") (pintype "passive"))
      (node (ref "U4") (pin "28") (pinfunction "DB13_28") (pintype "passive"))
    )
    (net (code "118") (name "/LCD_D14") (class "Default")
      (node (ref "U3") (pin "127") (pinfunction "127_127") (pintype "passive"))
      (node (ref "U4") (pin "29") (pinfunction "DB14_29") (pintype "passive"))
    )
    (net (code "119") (name "/LCD_D15") (class "Default")
      (node (ref "U3") (pin "142") (pinfunction "142_142") (pintype "passive"))
      (node (ref "U4") (pin "30") (pinfunction "DB15_30") (pintype "passive"))
    )
    (net (code "120") (name "/LCD_D16") (class "Default")
      (node (ref "U3") (pin "129") (pinfunction "129_129") (pintype "passive"))
      (node (ref "U4") (pin "31") (pinfunction "DB16_31") (pintype "passive"))
    )
    (net (code "121") (name "/LCD_D17") (class "Default")
      (node (ref "U3") (pin "144") (pinfunction "144_144") (pintype "passive"))
      (node (ref "U4") (pin "32") (pinfunction "DB17_32") (pintype "passive"))
    )
    (net (code "122") (name "/LCD_D18") (class "Default")
      (node (ref "U3") (pin "133") (pinfunction "133_133") (pintype "passive"))
      (node (ref "U4") (pin "33") (pinfunction "DB18_33") (pintype "passive"))
    )
    (net (code "123") (name "/LCD_D19") (class "Default")
      (node (ref "U3") (pin "4") (pinfunction "4_4") (pintype "passive"))
      (node (ref "U4") (pin "34") (pinfunction "DB19_34") (pintype "passive"))
    )
    (net (code "124") (name "/LCD_D20") (class "Default")
      (node (ref "U3") (pin "135") (pinfunction "135_135") (pintype "passive"))
      (node (ref "U4") (pin "35") (pinfunction "DB20_35") (pintype "passive"))
    )
    (net (code "125") (name "/LCD_D21") (class "Default")
      (node (ref "U3") (pin "3") (pinfunction "3_3") (pintype "passive"))
      (node (ref "U4") (pin "36") (pinfunction "DB21_36") (pintype "passive"))
    )
    (net (code "126") (name "/LCD_D22") (class "Default")
      (node (ref "U3") (pin "140") (pinfunction "140_140") (pintype "passive"))
      (node (ref "U4") (pin "37") (pinfunction "DB22_37") (pintype "passive"))
    )
    (net (code "127") (name "/LCD_D23") (class "Default")
      (node (ref "U3") (pin "1") (pinfunction "1_1") (pintype "passive"))
      (node (ref "U4") (pin "38") (pinfunction "DB23_38") (pintype "passive"))
    )
    (net (code "128") (name "/LCD_RD") (class "Default")
      (node (ref "U3") (pin "124") (pinfunction "124_124") (pintype "passive"))
      (node (ref "U4") (pin "12") (pinfunction "RD_12") (pintype "passive"))
    )
    (net (code "129") (name "/LCD_RS") (class "Default")
      (node (ref "U3") (pin "122") (pinfunction "122_122") (pintype "passive"))
      (node (ref "U4") (pin "10") (pinfunction "RS_10") (pintype "passive"))
    )
    (net (code "130") (name "/LCD_RST") (class "Default")
      (node (ref "U3") (pin "17") (pinfunction "17_17") (pintype "passive"))
      (node (ref "U4") (pin "13") (pinfunction "REST_13") (pintype "passive"))
      (node (ref "U4") (pin "55") (pinfunction "RST_55") (pintype "passive"))
    )
    (net (code "131") (name "/LCD_WR") (class "Default")
      (node (ref "U3") (pin "113") (pinfunction "113_113") (pintype "passive"))
      (node (ref "U4") (pin "11") (pinfunction "WR_11") (pintype "passive"))
    )
    (net (code "132") (name "/LED_B") (class "Default")
      (node (ref "D4") (pin "A") (pinfunction "A_A") (pintype "passive"))
      (node (ref "U1") (pin "9") (pinfunction "PC15-OSC32_OUT_9") (pintype "bidirectional"))
    )
    (net (code "133") (name "/LED_G") (class "Default")
      (node (ref "D3") (pin "A") (pinfunction "A_A") (pintype "passive"))
      (node (ref "U1") (pin "8") (pinfunction "PC14-OSC32_IN_8") (pintype "bidirectional"))
    )
    (net (code "134") (name "/LED_R") (class "Default")
      (node (ref "D2") (pin "A") (pinfunction "A_A") (pintype "passive"))
      (node (ref "U1") (pin "7") (pinfunction "PC13-TAMPER-RTC_7") (pintype "bidirectional"))
    )
    (net (code "135") (name "/LED_W") (class "Default")
      (node (ref "D6") (pin "A") (pinfunction "A_A") (pintype "passive"))
      (node (ref "U3") (pin "126") (pinfunction "126_126") (pintype "passive"))
    )
    (net (code "136") (name "/LED_Y") (class "Default")
      (node (ref "D7") (pin "A") (pinfunction "A_A") (pintype "passive"))
      (node (ref "U3") (pin "110") (pinfunction "110_110") (pintype "passive"))
    )
    (net (code "137") (name "/SDIO_CK") (class "Default")
      (node (ref "J1") (pin "5") (pinfunction "CLK_5") (pintype "passive"))
      (node (ref "U1") (pin "113") (pinfunction "SPI3_MOSI/SDIO_CK/UART5_TX/PC12_113") (pintype "bidirectional"))
    )
    (net (code "138") (name "/SDIO_CMD") (class "Default")
      (node (ref "J1") (pin "3") (pinfunction "CMD_3") (pintype "passive"))
      (node (ref "U1") (pin "116") (pinfunction "SDIO_CMD/UART5_RX//TIM3_ETR/PD2_116") (pintype "bidirectional"))
    )
    (net (code "139") (name "/SDIO_D0") (class "Default")
      (node (ref "J1") (pin "7") (pinfunction "DATA0_7") (pintype "passive"))
      (node (ref "U1") (pin "98") (pinfunction "SDIO_D0/TIM8_CH3/PC8_98") (pintype "bidirectional"))
    )
    (net (code "140") (name "/SDIO_D1") (class "Default")
      (node (ref "J1") (pin "8") (pinfunction "DATA1_8") (pintype "passive"))
      (node (ref "R5") (pin "1") (pinfunction "1_1") (pintype "passive"))
      (node (ref "U1") (pin "99") (pinfunction "I2C3_SDA/SDIO_D1/TIM8_CH4/PC9_99") (pintype "bidirectional"))
    )
    (net (code "141") (name "/SDIO_D2") (class "Default")
      (node (ref "J1") (pin "1") (pinfunction "DATA2_1") (pintype "passive"))
      (node (ref "U1") (pin "111") (pinfunction "USART3_TX/SDIO_D2/UART4_TX/PC10_111") (pintype "bidirectional"))
    )
    (net (code "142") (name "/SDIO_D3") (class "Default")
      (node (ref "J1") (pin "2") (pinfunction "CD/DATA3_2") (pintype "passive"))
      (node (ref "U1") (pin "112") (pinfunction "USART3_RX/SDIO_D3/UART4_RX/PC11_112") (pintype "bidirectional"))
    )
    (net (code "143") (name "/SDIO_INS") (class "Default")
      (node (ref "J1") (pin "9") (pinfunction "K_9") (pintype "passive"))
      (node (ref "U1") (pin "110") (pinfunction "I2S3_WS/SPI3_NSS//JTDI/PA15_110") (pintype "bidirectional"))
    )
    (net (code "144") (name "/SPI1_CS") (class "Default")
      (node (ref "U1") (pin "40") (pinfunction "PA4/SPI1_NSS/USART2_CK/ADC12_IN4_40") (pintype "bidirectional"))
      (node (ref "U3") (pin "94") (pinfunction "94_94") (pintype "passive"))
    )
    (net (code "145") (name "/SPI1_MISO") (class "Default")
      (node (ref "U1") (pin "42") (pinfunction "PA6/SPI1_MISO/ADC12_IN6/TIM3_CH1_42") (pintype "bidirectional"))
      (node (ref "U3") (pin "92") (pinfunction "92_92") (pintype "passive"))
    )
    (net (code "146") (name "/SPI1_MOSI") (class "Default")
      (node (ref "U1") (pin "43") (pinfunction "PA7/SPI1_MOSI/ADC12_IN7/TIM3_CH2_43") (pintype "bidirectional"))
      (node (ref "U3") (pin "91") (pinfunction "91_91") (pintype "passive"))
    )
    (net (code "147") (name "/SPI1_SCK") (class "Default")
      (node (ref "U1") (pin "41") (pinfunction "PA5/SPI1_SCK/ADC12_IN5_41") (pintype "bidirectional"))
      (node (ref "U3") (pin "93") (pinfunction "93_93") (pintype "passive"))
    )
    (net (code "148") (name "/SPI2_CS") (class "Default")
      (node (ref "P2") (pin "1") (pinfunction "1_1") (pintype "passive"))
      (node (ref "U1") (pin "73") (pinfunction "CAN2_RX/TIM1_BKIN/USART3_CK/I2C2_SMBAL/SPI2_NSS/PB12_73") (pintype "bidirectional"))
    )
    (net (code "149") (name "/SPI2_MISO") (class "Default")
      (node (ref "P2") (pin "3") (pinfunction "3_3") (pintype "passive"))
      (node (ref "U1") (pin "75") (pinfunction "TIM1_CH2N/USART3_RTS/SPI2_MISO/PB14_75") (pintype "bidirectional"))
    )
    (net (code "150") (name "/SPI2_MOSI") (class "Default")
      (node (ref "P2") (pin "4") (pinfunction "4_4") (pintype "passive"))
      (node (ref "U1") (pin "76") (pinfunction "TIM1_CH3N/SPI2_MOSI/PB15_76") (pintype "bidirectional"))
    )
    (net (code "151") (name "/SPI2_SCK") (class "Default")
      (node (ref "P2") (pin "2") (pinfunction "2_2") (pintype "passive"))
      (node (ref "U1") (pin "74") (pinfunction "CAN2_TX/PTIM1_CH1N/USART3_CTS/SPI2_SCK/B13_74") (pintype "bidirectional"))
    )
    (net (code "152") (name "/SPI5_CS") (class "Default")
      (node (ref "U1") (pin "18") (pinfunction "PF6/ADC3_IN4/FSMC_NIORD/UART7_RX_18") (pintype "bidirectional"))
      (node (ref "U5") (pin "1") (pinfunction "~{CS}_1") (pintype "passive"))
    )
    (net (code "153") (name "/SPI5_MISO") (class "Default")
      (node (ref "R6") (pin "1") (pinfunction "1_1") (pintype "passive"))
      (node (ref "U1") (pin "20") (pinfunction "PF8/ADC3_IN6/FSMC_NIOWR/SPI5_MISO_20") (pintype "bidirectional"))
    )
    (net (code "154") (name "/SPI5_MOSI") (class "Default")
      (node (ref "R7") (pin "2") (pinfunction "2_2") (pintype "passive"))
      (node (ref "U1") (pin "21") (pinfunction "PF9/ADC3_IN7/FSMC_CD/SPI5_MOSI_21") (pintype "bidirectional"))
    )
    (net (code "155") (name "/SPI5_SCK") (class "Default")
      (node (ref "U1") (pin "19") (pinfunction "PF7/ADC3_IN5/FSMC_NREG/UART7_TX/SPI5_SCK_19") (pintype "bidirectional"))
      (node (ref "U5") (pin "6") (pinfunction "CLK_6") (pintype "passive"))
    )
    (net (code "156") (name "/STM_OSCI") (class "Default")
      (node (ref "C9") (pin "1") (pinfunction "1_1") (pintype "passive"))
      (node (ref "U1") (pin "23") (pinfunction "OSC_IN_23") (pintype "input"))
      (node (ref "Y1") (pin "1") (pinfunction "OSC1_1") (pintype "passive"))
    )
    (net (code "157") (name "/STM_OSCO") (class "Default")
      (node (ref "C10") (pin "1") (pinfunction "1_1") (pintype "passive"))
      (node (ref "U1") (pin "24") (pinfunction "OSC_OUT_24") (pintype "output"))
      (node (ref "Y1") (pin "2") (pinfunction "OSC2_2") (pintype "passive"))
    )
    (net (code "158") (name "/STM_RST") (class "Default")
      (node (ref "B2") (pin "2") (pinfunction "2_2") (pintype "passive"))
      (node (ref "C8") (pin "2") (pinfunction "2_2") (pintype "passive"))
      (node (ref "JP1") (pin "1") (pinfunction "NRST_1") (pintype "passive"))
      (node (ref "R16") (pin "1") (pinfunction "1_1") (pintype "passive"))
      (node (ref "U1") (pin "25") (pinfunction "NRST_25") (pintype "bidirectional"))
    )
    (net (code "159") (name "/STM_SWCLK") (class "Default")
      (node (ref "JP1") (pin "2") (pinfunction "SWCLK_2") (pintype "passive"))
      (node (ref "U1") (pin "109") (pinfunction "SWCLK/JTCK/PA14_109") (pintype "bidirectional"))
    )
    (net (code "160") (name "/STM_SWDIO") (class "Default")
      (node (ref "JP1") (pin "4") (pinfunction "SWDIO_4") (pintype "passive"))
      (node (ref "U1") (pin "105") (pinfunction "SWDIO/JTMS/PA13_105") (pintype "bidirectional"))
    )
    (net (code "161") (name "/SYS_LED") (class "Default")
      (node (ref "D5") (pin "1") (pinfunction "1_1") (pintype "passive"))
      (node (ref "D5") (pin "3") (pinfunction "3_3") (pintype "passive"))
      (node (ref "U1") (pin "27") (pinfunction "PC1/ADC12_IN11_27") (pintype "bidirectional"))
    )
    (net (code "162") (name "/USART1_RX") (class "Default")
      (node (ref "U1") (pin "102") (pinfunction "TIM1_CH3/USART1_RX/PA10_102") (pintype "bidirectional"))
      (node (ref "U3") (pin "39") (pinfunction "39_39") (pintype "passive"))
    )
    (net (code "163") (name "/USART1_TX") (class "Default")
      (node (ref "U1") (pin "101") (pinfunction "TIM1_CH2/USART1_TX/PA9_101") (pintype "bidirectional"))
      (node (ref "U3") (pin "57") (pinfunction "57_57") (pintype "passive"))
    )
    (net (code "164") (name "/USART2_RX") (class "Default")
      (node (ref "P2") (pin "7") (pinfunction "7_7") (pintype "passive"))
      (node (ref "U1") (pin "37") (pinfunction "PA3/USART2_RX/ADC12_IN3/TIM2_CH4_37") (pintype "bidirectional"))
    )
    (net (code "165") (name "/USART2_TX") (class "Default")
      (node (ref "P2") (pin "8") (pinfunction "8_8") (pintype "passive"))
      (node (ref "U1") (pin "36") (pinfunction "PA2/USART2_TX/ADC12_IN2/TIM2_CH3_36") (pintype "bidirectional"))
    )
    (net (code "166") (name "/USART6_RX") (class "Default")
      (node (ref "P4") (pin "2") (pinfunction "RxD_2") (pintype "passive"))
      (node (ref "U1") (pin "97") (pinfunction "USART6_RX/SDIO_D7/TIM8_CH2/I2S3_MCK/PC7_97") (pintype "bidirectional"))
    )
    (net (code "167") (name "/USART6_TX") (class "Default")
      (node (ref "P4") (pin "3") (pinfunction "TxD_3") (pintype "passive"))
      (node (ref "U1") (pin "96") (pinfunction "USART6_TX/SDIO_D6/TIM8_CH1/I2S2_MCK/PC6_96") (pintype "bidirectional"))
    )
    (net (code "168") (name "/USB_DM") (class "Default")
      (node (ref "R28") (pin "2") (pinfunction "2_2") (pintype "passive"))
      (node (ref "U1") (pin "103") (pinfunction "USBDM/TIM1_CH4/CAN1_RX/USART1_CTS/PA11_103") (pintype "bidirectional"))
    )
    (net (code "169") (name "/USB_DP") (class "Default")
      (node (ref "R27") (pin "2") (pinfunction "2_2") (pintype "passive"))
      (node (ref "U1") (pin "104") (pinfunction "USBDP/TIM1_ETR/CAN1_TX/USART1_RTS/PA12_104") (pintype "bidirectional"))
    )
    (net (code "170") (name "FPGA_1V2") (class "Default")
      (node (ref "C2") (pin "1") (pinfunction "1_1") (pintype "passive"))
      (node (ref "C22") (pin "2") (pinfunction "2_2") (pintype "passive"))
      (node (ref "C23") (pin "2") (pinfunction "2_2") (pintype "passive"))
      (node (ref "C6") (pin "2") (pinfunction "2_2") (pintype "passive"))
      (node (ref "L1") (pin "2") (pinfunction "2_2") (pintype "passive"))
      (node (ref "L2") (pin "1") (pinfunction "1_1") (pintype "passive"))
      (node (ref "U3") (pin "117") (pinfunction "VCORE_5_117") (pintype "passive"))
      (node (ref "U3") (pin "132") (pinfunction "VCORE_3_132") (pintype "passive"))
      (node (ref "U3") (pin "143") (pinfunction "VCORE_4_143") (pintype "passive"))
      (node (ref "U3") (pin "38") (pinfunction "VCORE_38") (pintype "passive"))
      (node (ref "U3") (pin "47") (pinfunction "VCORE1_47") (pintype "passive"))
      (node (ref "U3") (pin "63") (pinfunction "VCORE2_63") (pintype "passive"))
      (node (ref "VR4") (pin "2") (pinfunction "Vout_2") (pintype "passive"))
    )
    (net (code "171") (name "FPGA_3V3") (class "Default")
      (node (ref "BEEP1") (pin "1") (pinfunction "+_1") (pintype "passive"))
      (node (ref "BEEP2") (pin "1") (pinfunction "+_1") (pintype "passive"))
      (node (ref "C13") (pin "2") (pinfunction "2_2") (pintype "passive"))
      (node (ref "C15") (pin "2") (pinfunction "2_2") (pintype "passive"))
      (node (ref "R2") (pin "1") (pinfunction "1_1") (pintype "passive"))
      (node (ref "R3") (pin "2") (pinfunction "2_2") (pintype "passive"))
      (node (ref "U3") (pin "114") (pinfunction "VCCIO7_114") (pintype "passive"))
      (node (ref "U3") (pin "120") (pinfunction "VCCIO7_1_120") (pintype "passive"))
      (node (ref "U3") (pin "136") (pinfunction "VCCIO8_136") (pintype "passive"))
      (node (ref "U3") (pin "139") (pinfunction "VCCIO8_1_139") (pintype "passive"))
      (node (ref "U3") (pin "20") (pinfunction "VCCIO1_20") (pintype "passive"))
      (node (ref "U3") (pin "27") (pinfunction "VCCIO2_27") (pintype "passive"))
      (node (ref "U3") (pin "41") (pinfunction "VCCIO3_41") (pintype "passive"))
      (node (ref "U3") (pin "49") (pinfunction "VCCIO3_1_49") (pintype "passive"))
      (node (ref "U3") (pin "56") (pinfunction "VCCIO3_2_56") (pintype "passive"))
      (node (ref "U3") (pin "64") (pinfunction "VCCIO4_64") (pintype "passive"))
      (node (ref "U3") (pin "68") (pinfunction "VCCIO4_1_68") (pintype "passive"))
      (node (ref "U3") (pin "72") (pinfunction "VCCAUX_72") (pintype "passive"))
      (node (ref "U3") (pin "83") (pinfunction "VCCIO5_83") (pintype "passive"))
      (node (ref "U3") (pin "95") (pinfunction "VCCIO6_95") (pintype "passive"))
      (node (ref "U6") (pin "3") (pinfunction "~{WP}_3") (pintype "passive"))
      (node (ref "U6") (pin "7") (pinfunction "~{HOLD}_7") (pintype "passive"))
      (node (ref "U6") (pin "8") (pinfunction "VCC_8") (pintype "passive"))
      (node (ref "U7") (pin "3") (pinfunction "~{WP}_3") (pintype "passive"))
      (node (ref "U7") (pin "7") (pinfunction "~{HOLD}_7") (pintype "passive"))
      (node (ref "U7") (pin "8") (pinfunction "VCC_8") (pintype "passive"))
      (node (ref "VR2") (pin "2") (pinfunction "Vout_2") (pintype "passive"))
    )
    (net (code "172") (name "GND") (class "Default")
      (node (ref "B1") (pin "2") (pinfunction "2_2") (pintype "passive"))
      (node (ref "B2") (pin "1") (pinfunction "1_1") (pintype "passive"))
      (node (ref "C1") (pin "2") (pinfunction "2_2") (pintype "passive"))
      (node (ref "C10") (pin "2") (pinfunction "2_2") (pintype "passive"))
      (node (ref "C11") (pin "1") (pinfunction "1_1") (pintype "passive"))
      (node (ref "C12") (pin "1") (pinfunction "1_1") (pintype "passive"))
      (node (ref "C13") (pin "1") (pinfunction "1_1") (pintype "passive"))
      (node (ref "C14") (pin "2") (pinfunction "2_2") (pintype "passive"))
      (node (ref "C15") (pin "1") (pinfunction "1_1") (pintype "passive"))
      (node (ref "C16") (pin "2") (pinfunction "2_2") (pintype "passive"))
      (node (ref "C17") (pin "1") (pinfunction "1_1") (pintype "passive"))
      (node (ref "C18") (pin "1") (pinfunction "1_1") (pintype "passive"))
      (node (ref "C19") (pin "1") (pinfunction "1_1") (pintype "passive"))
      (node (ref "C2") (pin "2") (pinfunction "2_2") (pintype "passive"))
      (node (ref "C20") (pin "1") (pinfunction "1_1") (pintype "passive"))
      (node (ref "C21") (pin "1") (pinfunction "1_1") (pintype "passive"))
      (node (ref "C22") (pin "1") (pinfunction "1_1") (pintype "passive"))
      (node (ref "C23") (pin "1") (pinfunction "1_1") (pintype "passive"))
      (node (ref "C3") (pin "2") (pinfunction "2_2") (pintype "passive"))
      (node (ref "C4") (pin "2") (pinfunction "2_2") (pintype "passive"))
      (node (ref "C5") (pin "1") (pinfunction "1_1") (pintype "passive"))
      (node (ref "C6") (pin "1") (pinfunction "1_1") (pintype "passive"))
      (node (ref "C7") (pin "1") (pinfunction "1_1") (pintype "passive"))
      (node (ref "C8") (pin "1") (pinfunction "1_1") (pintype "passive"))
      (node (ref "C9") (pin "2") (pinfunction "2_2") (pintype "passive"))
      (node (ref "D1") (pin "K") (pinfunction "K_K") (pintype "passive"))
      (node (ref "J1") (pin "10") (pinfunction "GND_10") (pintype "passive"))
      (node (ref "J1") (pin "6") (pinfunction "VSS_6") (pintype "passive"))
      (node (ref "JP1") (pin "3") (pinfunction "GND_3") (pintype "passive"))
      (node (ref "JP2") (pin "3") (pinfunction "GND_3") (pintype "passive"))
      (node (ref "P1") (pin "2") (pinfunction "2_2") (pintype "passive"))
      (node (ref "P1") (pin "4") (pinfunction "4_4") (pintype "passive"))
      (node (ref "P1") (pin "6") (pinfunction "6_6") (pintype "passive"))
      (node (ref "P1") (pin "8") (pinfunction "8_8") (pintype "passive"))
      (node (ref "P3") (pin "2") (pinfunction "2_2") (pintype "passive"))
      (node (ref "P3") (pin "4") (pinfunction "4_4") (pintype "passive"))
      (node (ref "P3") (pin "6") (pinfunction "6_6") (pintype "passive"))
      (node (ref "P3") (pin "8") (pinfunction "8_8") (pintype "passive"))
      (node (ref "P4") (pin "1") (pinfunction "GND_1") (pintype "passive"))
      (node (ref "Q1") (pin "2") (pinfunction "E_2") (pintype "passive"))
      (node (ref "Q2") (pin "2") (pinfunction "E_2") (pintype "passive"))
      (node (ref "R1") (pin "2") (pinfunction "2_2") (pintype "passive"))
      (node (ref "R15") (pin "2") (pinfunction "2_2") (pintype "passive"))
      (node (ref "R17") (pin "2") (pinfunction "2_2") (pintype "passive"))
      (node (ref "R19") (pin "1") (pinfunction "1_1") (pintype "passive"))
      (node (ref "R20") (pin "2") (pinfunction "2_2") (pintype "passive"))
      (node (ref "R22") (pin "2") (pinfunction "2_2") (pintype "passive"))
      (node (ref "R24") (pin "1") (pinfunction "1_1") (pintype "passive"))
      (node (ref "R25") (pin "2") (pinfunction "2_2") (pintype "passive"))
      (node (ref "R26") (pin "1") (pinfunction "1_1") (pintype "passive"))
      (node (ref "R8") (pin "2") (pinfunction "2_2") (pintype "passive"))
      (node (ref "SW1") (pin "2") (pinfunction "2_2") (pintype "passive"))
      (node (ref "SW2") (pin "2") (pinfunction "2_2") (pintype "passive"))
      (node (ref "SW3") (pin "2") (pinfunction "2_2") (pintype "passive"))
      (node (ref "SW4") (pin "2") (pinfunction "2_2") (pintype "passive"))
      (node (ref "SW5") (pin "2") (pinfunction "2_2") (pintype "passive"))
      (node (ref "SW6") (pin "2") (pinfunction "2_2") (pintype "passive"))
      (node (ref "SW7") (pin "2") (pinfunction "2_2") (pintype "passive"))
      (node (ref "SW8") (pin "2") (pinfunction "2_2") (pintype "passive"))
      (node (ref "U1") (pin "107") (pinfunction "VSS_2_107") (pintype "power_in"))
      (node (ref "U1") (pin "120") (pinfunction "VSS_10_120") (pintype "power_in"))
      (node (ref "U1") (pin "130") (pinfunction "VSS_11_130") (pintype "power_in"))
      (node (ref "U1") (pin "16") (pinfunction "VSS_5_16") (pintype "power_in"))
      (node (ref "U1") (pin "31") (pinfunction "VSSA_31") (pintype "power_in"))
      (node (ref "U1") (pin "38") (pinfunction "VSS_4_38") (pintype "power_in"))
      (node (ref "U1") (pin "51") (pinfunction "VSS_6_51") (pintype "power_in"))
      (node (ref "U1") (pin "61") (pinfunction "VSS_7_61") (pintype "power_in"))
      (node (ref "U1") (pin "83") (pinfunction "VSS_8_83") (pintype "power_in"))
      (node (ref "U1") (pin "94") (pinfunction "VSS_9_94") (pintype "power_in"))
      (node (ref "U2") (pin "12") (pinfunction "VSSQ_12") (pintype "power_in"))
      (node (ref "U2") (pin "28") (pinfunction "VSS_28") (pintype "power_in"))
      (node (ref "U2") (pin "41") (pinfunction "VSS_41") (pintype "power_in"))
      (node (ref "U2") (pin "46") (pinfunction "VSSQ_46") (pintype "power_in"))
      (node (ref "U2") (pin "52") (pinfunction "VSSQ_52") (pintype "power_in"))
      (node (ref "U2") (pin "54") (pinfunction "VSS_54") (pintype "power_in"))
      (node (ref "U2") (pin "6") (pinfunction "VSSQ_6") (pintype "power_in"))
      (node (ref "U3") (pin "50") (pinfunction "GND1_50") (pintype "passive"))
      (node (ref "U3") (pin "EGND") (pinfunction "GND_EGND") (pintype "passive"))
      (node (ref "U4") (pin "1") (pinfunction "GND_1") (pintype "passive"))
      (node (ref "U4") (pin "14") (pinfunction "GND_14") (pintype "passive"))
      (node (ref "U4") (pin "39") (pinfunction "GND_39") (pintype "passive"))
      (node (ref "U4") (pin "4") (pinfunction "IM0_4") (pintype "passive"))
      (node (ref "U4") (pin "52") (pinfunction "PAD_52") (pintype "passive"))
      (node (ref "U4") (pin "53") (pinfunction "PAD_53") (pintype "passive"))
      (node (ref "U4") (pin "59") (pinfunction "GND_59") (pintype "passive"))
      (node (ref "U4") (pin "6") (pinfunction "IM2_6") (pintype "passive"))
      (node (ref "U5") (pin "4") (pinfunction "GND_4") (pintype "passive"))
      (node (ref "U6") (pin "4") (pinfunction "GND_4") (pintype "passive"))
      (node (ref "U7") (pin "4") (pinfunction "GND_4") (pintype "passive"))
      (node (ref "U8") (pin "2") (pinfunction "GND_2") (pintype "passive"))
      (node (ref "USB1") (pin "5") (pinfunction "GND_5") (pintype "passive"))
      (node (ref "VR1") (pin "1") (pinfunction "GND_1") (pintype "passive"))
      (node (ref "VR2") (pin "1") (pinfunction "GND_1") (pintype "passive"))
      (node (ref "VR3") (pin "1") (pinfunction "GND_1") (pintype "passive"))
      (node (ref "VR4") (pin "1") (pinfunction "GND_1") (pintype "passive"))
    )
    (net (code "173") (name "LCD_3V3") (class "Default")
      (node (ref "C18") (pin "2") (pinfunction "2_2") (pintype "passive"))
      (node (ref "C19") (pin "2") (pinfunction "2_2") (pintype "passive"))
      (node (ref "P3") (pin "1") (pinfunction "1_1") (pintype "passive"))
      (node (ref "P3") (pin "3") (pinfunction "3_3") (pintype "passive"))
      (node (ref "P3") (pin "5") (pinfunction "5_5") (pintype "passive"))
      (node (ref "P3") (pin "7") (pinfunction "7_7") (pintype "passive"))
      (node (ref "R12") (pin "2") (pinfunction "2_2") (pintype "passive"))
      (node (ref "R9") (pin "2") (pinfunction "2_2") (pintype "passive"))
      (node (ref "U4") (pin "2") (pinfunction "VCC_2") (pintype "passive"))
      (node (ref "U4") (pin "3") (pinfunction "VCC_3") (pintype "passive"))
      (node (ref "U4") (pin "5") (pinfunction "IM1_5") (pintype "passive"))
      (node (ref "U4") (pin "54") (pinfunction "VCC_54") (pintype "passive"))
      (node (ref "VR3") (pin "2") (pinfunction "Vout_2") (pintype "passive"))
    )
    (net (code "174") (name "Net-(BEEP1--)") (class "Default")
      (node (ref "BEEP1") (pin "2") (pinfunction "-_2") (pintype "passive"))
      (node (ref "Q1") (pin "3") (pinfunction "C_3") (pintype "passive"))
    )
    (net (code "175") (name "Net-(BEEP2--)") (class "Default")
      (node (ref "BEEP2") (pin "2") (pinfunction "-_2") (pintype "passive"))
      (node (ref "Q2") (pin "3") (pinfunction "C_3") (pintype "passive"))
    )
    (net (code "176") (name "Net-(D2-PadK)") (class "Default")
      (node (ref "D2") (pin "K") (pinfunction "K_K") (pintype "passive"))
      (node (ref "R8") (pin "1") (pinfunction "1_1") (pintype "passive"))
    )
    (net (code "177") (name "Net-(D3-PadK)") (class "Default")
      (node (ref "D3") (pin "K") (pinfunction "K_K") (pintype "passive"))
      (node (ref "R15") (pin "1") (pinfunction "1_1") (pintype "passive"))
    )
    (net (code "178") (name "Net-(D4-PadK)") (class "Default")
      (node (ref "D4") (pin "K") (pinfunction "K_K") (pintype "passive"))
      (node (ref "R17") (pin "1") (pinfunction "1_1") (pintype "passive"))
    )
    (net (code "179") (name "Net-(D5-Pad2)") (class "Default")
      (node (ref "D5") (pin "2") (pinfunction "2_2") (pintype "passive"))
      (node (ref "R18") (pin "1") (pinfunction "1_1") (pintype "passive"))
    )
    (net (code "180") (name "Net-(D5-Pad4)") (class "Default")
      (node (ref "D5") (pin "4") (pinfunction "4_4") (pintype "passive"))
      (node (ref "R19") (pin "2") (pinfunction "2_2") (pintype "passive"))
    )
    (net (code "181") (name "Net-(D6-PadK)") (class "Default")
      (node (ref "D6") (pin "K") (pinfunction "K_K") (pintype "passive"))
      (node (ref "R20") (pin "1") (pinfunction "1_1") (pintype "passive"))
    )
    (net (code "182") (name "Net-(D7-PadK)") (class "Default")
      (node (ref "D7") (pin "K") (pinfunction "K_K") (pintype "passive"))
      (node (ref "R22") (pin "1") (pinfunction "1_1") (pintype "passive"))
    )
    (net (code "183") (name "Net-(D8-A)") (class "Default")
      (node (ref "D8") (pin "1") (pinfunction "A_1") (pintype "passive"))
      (node (ref "L3") (pin "1") (pinfunction "1_1") (pintype "passive"))
      (node (ref "U8") (pin "1") (pinfunction "SW_1") (pintype "passive"))
    )
    (net (code "184") (name "Net-(D8-K)") (class "Default")
      (node (ref "C17") (pin "2") (pinfunction "2_2") (pintype "passive"))
      (node (ref "D8") (pin "2") (pinfunction "K_2") (pintype "passive"))
      (node (ref "U4") (pin "50") (pinfunction "A_50") (pintype "passive"))
      (node (ref "U4") (pin "51") (pinfunction "A_51") (pintype "passive"))
    )
    (net (code "185") (name "Net-(D9-PadK)") (class "Default")
      (node (ref "D9") (pin "K") (pinfunction "K_K") (pintype "passive"))
      (node (ref "R26") (pin "2") (pinfunction "2_2") (pintype "passive"))
    )
    (net (code "186") (name "Net-(PLD1-Pad2)") (class "Default")
      (node (ref "PLD1") (pin "2") (pinfunction "2_2") (pintype "passive"))
      (node (ref "PLU1") (pin "3") (pinfunction "3_3") (pintype "passive"))
    )
    (net (code "187") (name "Net-(PLD1-Pad3)") (class "Default")
      (node (ref "PLD1") (pin "3") (pinfunction "3_3") (pintype "passive"))
      (node (ref "PLL1") (pin "2") (pinfunction "2_2") (pintype "passive"))
    )
    (net (code "188") (name "Net-(PLL1-Pad3)") (class "Default")
      (node (ref "PLL1") (pin "3") (pinfunction "3_3") (pintype "passive"))
      (node (ref "PLR1") (pin "2") (pinfunction "2_2") (pintype "passive"))
    )
    (net (code "189") (name "Net-(PRD1-Pad2)") (class "Default")
      (node (ref "PRD1") (pin "2") (pinfunction "2_2") (pintype "passive"))
      (node (ref "PRU1") (pin "3") (pinfunction "3_3") (pintype "passive"))
    )
    (net (code "190") (name "Net-(PRD1-Pad3)") (class "Default")
      (node (ref "PRD1") (pin "3") (pinfunction "3_3") (pintype "passive"))
      (node (ref "PRL1") (pin "2") (pinfunction "2_2") (pintype "passive"))
    )
    (net (code "191") (name "Net-(PRL1-Pad3)") (class "Default")
      (node (ref "PRL1") (pin "3") (pinfunction "3_3") (pintype "passive"))
      (node (ref "PRR1") (pin "2") (pinfunction "2_2") (pintype "passive"))
    )
    (net (code "192") (name "Net-(Q1-B)") (class "Default")
      (node (ref "Q1") (pin "1") (pinfunction "B_1") (pintype "passive"))
      (node (ref "R21") (pin "2") (pinfunction "2_2") (pintype "passive"))
    )
    (net (code "193") (name "Net-(Q2-B)") (class "Default")
      (node (ref "Q2") (pin "1") (pinfunction "B_1") (pintype "passive"))
      (node (ref "R23") (pin "2") (pinfunction "2_2") (pintype "passive"))
    )
    (net (code "194") (name "Net-(U1-BOOT0)") (class "Default")
      (node (ref "R1") (pin "1") (pinfunction "1_1") (pintype "passive"))
      (node (ref "U1") (pin "138") (pinfunction "BOOT0_138") (pintype "bidirectional"))
    )
    (net (code "195") (name "Net-(U1-I2C3_SCL{slash}MCO1{slash}TIM1_CH1{slash}USART1_CK{slash}PA8)") (class "Default")
      (node (ref "R4") (pin "1") (pinfunction "1_1") (pintype "passive"))
      (node (ref "U1") (pin "100") (pinfunction "I2C3_SCL/MCO1/TIM1_CH1/USART1_CK/PA8_100") (pintype "bidirectional"))
    )
    (net (code "196") (name "Net-(U1-VCAP_1)") (class "Default")
      (node (ref "C7") (pin "2") (pinfunction "2_2") (pintype "passive"))
      (node (ref "U1") (pin "71") (pinfunction "VCAP_1_71") (pintype "power_in"))
    )
    (net (code "197") (name "Net-(U1-VCAP_2)") (class "Default")
      (node (ref "C3") (pin "1") (pinfunction "1_1") (pintype "passive"))
      (node (ref "U1") (pin "106") (pinfunction "VCAP_2_106") (pintype "tri_state"))
    )
    (net (code "198") (name "Net-(U3-VCC_PLL)") (class "Default")
      (node (ref "C4") (pin "1") (pinfunction "1_1") (pintype "passive"))
      (node (ref "L1") (pin "1") (pinfunction "1_1") (pintype "passive"))
      (node (ref "U3") (pin "109") (pinfunction "VCC_PLL_109") (pintype "passive"))
    )
    (net (code "199") (name "Net-(U3-VCC_PLL1)") (class "Default")
      (node (ref "C5") (pin "2") (pinfunction "2_2") (pintype "passive"))
      (node (ref "L2") (pin "2") (pinfunction "2_2") (pintype "passive"))
      (node (ref "U3") (pin "37") (pinfunction "VCC_PLL1_37") (pintype "passive"))
    )
    (net (code "200") (name "Net-(U3-{slash}INIT)") (class "Default")
      (node (ref "D1") (pin "A") (pinfunction "A_A") (pintype "passive"))
      (node (ref "R2") (pin "2") (pinfunction "2_2") (pintype "passive"))
      (node (ref "U3") (pin "9") (pinfunction "/INIT_9") (pintype "passive"))
    )
    (net (code "201") (name "Net-(U4A-K1)") (class "Default")
      (node (ref "R24") (pin "2") (pinfunction "2_2") (pintype "passive"))
      (node (ref "U4") (pin "45") (pinfunction "K1_45") (pintype "passive"))
      (node (ref "U4") (pin "46") (pinfunction "K2_46") (pintype "passive"))
      (node (ref "U4") (pin "47") (pinfunction "K3_47") (pintype "passive"))
      (node (ref "U4") (pin "48") (pinfunction "K4_48") (pintype "passive"))
      (node (ref "U4") (pin "49") (pinfunction "K5_49") (pintype "passive"))
      (node (ref "U8") (pin "3") (pinfunction "FB_3") (pintype "passive"))
    )
    (net (code "202") (name "Net-(U5-DI)") (class "Default")
      (node (ref "R7") (pin "1") (pinfunction "1_1") (pintype "passive"))
      (node (ref "U5") (pin "5") (pinfunction "DI_5") (pintype "passive"))
    )
    (net (code "203") (name "Net-(U5-DO)") (class "Default")
      (node (ref "R6") (pin "2") (pinfunction "2_2") (pintype "passive"))
      (node (ref "U5") (pin "2") (pinfunction "DO_2") (pintype "passive"))
    )
    (net (code "204") (name "Net-(U6-DI)") (class "Default")
      (node (ref "R13") (pin "1") (pinfunction "1_1") (pintype "passive"))
      (node (ref "U6") (pin "5") (pinfunction "DI_5") (pintype "passive"))
    )
    (net (code "205") (name "Net-(U6-DO)") (class "Default")
      (node (ref "R10") (pin "2") (pinfunction "2_2") (pintype "passive"))
      (node (ref "U6") (pin "2") (pinfunction "DO_2") (pintype "passive"))
    )
    (net (code "206") (name "Net-(U7-DI)") (class "Default")
      (node (ref "R14") (pin "1") (pinfunction "1_1") (pintype "passive"))
      (node (ref "U7") (pin "5") (pinfunction "DI_5") (pintype "passive"))
    )
    (net (code "207") (name "Net-(U7-DO)") (class "Default")
      (node (ref "R11") (pin "2") (pinfunction "2_2") (pintype "passive"))
      (node (ref "U7") (pin "2") (pinfunction "DO_2") (pintype "passive"))
    )
    (net (code "208") (name "Net-(USB1-+5V)") (class "Default")
      (node (ref "S1") (pin "2") (pinfunction "2_2") (pintype "passive"))
      (node (ref "USB1") (pin "1") (pinfunction "+5V_1") (pintype "passive"))
    )
    (net (code "209") (name "Net-(USB1-D+)") (class "Default")
      (node (ref "R27") (pin "1") (pinfunction "1_1") (pintype "passive"))
      (node (ref "USB1") (pin "3") (pinfunction "D+_3") (pintype "passive"))
    )
    (net (code "210") (name "Net-(USB1-D-)") (class "Default")
      (node (ref "R28") (pin "1") (pinfunction "1_1") (pintype "passive"))
      (node (ref "USB1") (pin "2") (pinfunction "D-_2") (pintype "passive"))
    )
    (net (code "211") (name "Net-(USB1-ID)") (class "Default")
      (node (ref "R25") (pin "1") (pinfunction "1_1") (pintype "passive"))
      (node (ref "USB1") (pin "4") (pinfunction "ID_4") (pintype "passive"))
    )
    (net (code "212") (name "STM_3V3") (class "Default")
      (node (ref "C11") (pin "2") (pinfunction "2_2") (pintype "passive"))
      (node (ref "C12") (pin "2") (pinfunction "2_2") (pintype "passive"))
      (node (ref "J1") (pin "4") (pinfunction "VDD_4") (pintype "passive"))
      (node (ref "JP1") (pin "5") (pinfunction "VCC_5") (pintype "passive"))
      (node (ref "P4") (pin "4") (pinfunction "VCC_4") (pintype "passive"))
      (node (ref "R16") (pin "2") (pinfunction "2_2") (pintype "passive"))
      (node (ref "R18") (pin "2") (pinfunction "2_2") (pintype "passive"))
      (node (ref "U1") (pin "108") (pinfunction "VDD_2_108") (pintype "power_in"))
      (node (ref "U1") (pin "121") (pinfunction "VDD_10_121") (pintype "power_in"))
      (node (ref "U1") (pin "131") (pinfunction "VDD_11_131") (pintype "power_in"))
      (node (ref "U1") (pin "143") (pinfunction "PDR_ON_143") (pintype "power_in"))
      (node (ref "U1") (pin "144") (pinfunction "VDD_3_144") (pintype "power_in"))
      (node (ref "U1") (pin "17") (pinfunction "VDD_5_17") (pintype "power_in"))
      (node (ref "U1") (pin "30") (pinfunction "VDD_30") (pintype "power_in"))
      (node (ref "U1") (pin "32") (pinfunction "VREF+_32") (pintype "power_in"))
      (node (ref "U1") (pin "33") (pinfunction "VDDA_33") (pintype "power_in"))
      (node (ref "U1") (pin "39") (pinfunction "VDD_4_39") (pintype "power_in"))
      (node (ref "U1") (pin "52") (pinfunction "VDD_6_52") (pintype "power_in"))
      (node (ref "U1") (pin "6") (pinfunction "VBAT_6") (pintype "power_in"))
      (node (ref "U1") (pin "62") (pinfunction "VDD_7_62") (pintype "power_in"))
      (node (ref "U1") (pin "72") (pinfunction "VDD_1_72") (pintype "power_in"))
      (node (ref "U1") (pin "84") (pinfunction "VDD_8_84") (pintype "power_in"))
      (node (ref "U1") (pin "95") (pinfunction "VDD_9_95") (pintype "power_in"))
      (node (ref "U2") (pin "1") (pinfunction "VDD_1") (pintype "power_in"))
      (node (ref "U2") (pin "14") (pinfunction "VDD_14") (pintype "power_in"))
      (node (ref "U2") (pin "27") (pinfunction "VDD_27") (pintype "power_in"))
      (node (ref "U2") (pin "3") (pinfunction "VDDQ_3") (pintype "power_in"))
      (node (ref "U2") (pin "43") (pinfunction "VDDQ_43") (pintype "power_in"))
      (node (ref "U2") (pin "49") (pinfunction "VDDQ_49") (pintype "power_in"))
      (node (ref "U2") (pin "9") (pinfunction "VDDQ_9") (pintype "power_in"))
      (node (ref "U5") (pin "3") (pinfunction "~{WP}_3") (pintype "passive"))
      (node (ref "U5") (pin "7") (pinfunction "~{HOLD}_ro_~{RESET}_7") (pintype "passive"))
      (node (ref "U5") (pin "8") (pinfunction "VCC_8") (pintype "passive"))
      (node (ref "VR1") (pin "2") (pinfunction "Vout_2") (pintype "passive"))
    )
    (net (code "213") (name "U5V") (class "Default")
      (node (ref "C14") (pin "1") (pinfunction "1_1") (pintype "passive"))
      (node (ref "C16") (pin "1") (pinfunction "1_1") (pintype "passive"))
      (node (ref "C20") (pin "2") (pinfunction "2_2") (pintype "passive"))
      (node (ref "C21") (pin "2") (pinfunction "2_2") (pintype "passive"))
      (node (ref "D9") (pin "A") (pinfunction "A_A") (pintype "passive"))
      (node (ref "L3") (pin "2") (pinfunction "2_2") (pintype "passive"))
      (node (ref "P1") (pin "1") (pinfunction "1_1") (pintype "passive"))
      (node (ref "P1") (pin "3") (pinfunction "3_3") (pintype "passive"))
      (node (ref "P1") (pin "5") (pinfunction "5_5") (pintype "passive"))
      (node (ref "P1") (pin "7") (pinfunction "7_7") (pintype "passive"))
      (node (ref "S1") (pin "1") (pinfunction "1_1") (pintype "passive"))
      (node (ref "U8") (pin "5") (pinfunction "IN_5") (pintype "passive"))
      (node (ref "VR1") (pin "3") (pinfunction "Vin_3") (pintype "passive"))
      (node (ref "VR2") (pin "3") (pinfunction "Vin_3") (pintype "passive"))
      (node (ref "VR3") (pin "3") (pinfunction "Vin_3") (pintype "passive"))
      (node (ref "VR4") (pin "3") (pinfunction "Vin_3") (pintype "passive"))
    )
    (net (code "214") (name "unconnected-(PLD1-Pad1)") (class "Default")
      (node (ref "PLD1") (pin "1") (pinfunction "1_1") (pintype "passive"))
    )
    (net (code "215") (name "unconnected-(PLL1-Pad1)") (class "Default")
      (node (ref "PLL1") (pin "1") (pinfunction "1_1") (pintype "passive"))
    )
    (net (code "216") (name "unconnected-(PLR1-Pad1)") (class "Default")
      (node (ref "PLR1") (pin "1") (pinfunction "1_1") (pintype "passive"))
    )
    (net (code "217") (name "unconnected-(PLR1-Pad3)") (class "Default")
      (node (ref "PLR1") (pin "3") (pinfunction "3_3") (pintype "passive"))
    )
    (net (code "218") (name "unconnected-(PLU1-Pad1)") (class "Default")
      (node (ref "PLU1") (pin "1") (pinfunction "1_1") (pintype "passive"))
    )
    (net (code "219") (name "unconnected-(PRD1-Pad1)") (class "Default")
      (node (ref "PRD1") (pin "1") (pinfunction "1_1") (pintype "passive"))
    )
    (net (code "220") (name "unconnected-(PRL1-Pad1)") (class "Default")
      (node (ref "PRL1") (pin "1") (pinfunction "1_1") (pintype "passive"))
    )
    (net (code "221") (name "unconnected-(PRR1-Pad1)") (class "Default")
      (node (ref "PRR1") (pin "1") (pinfunction "1_1") (pintype "passive"))
    )
    (net (code "222") (name "unconnected-(PRR1-Pad3)") (class "Default")
      (node (ref "PRR1") (pin "3") (pinfunction "3_3") (pintype "passive"))
    )
    (net (code "223") (name "unconnected-(PRU1-Pad1)") (class "Default")
      (node (ref "PRU1") (pin "1") (pinfunction "1_1") (pintype "passive"))
    )
    (net (code "224") (name "unconnected-(S1-Pad3)") (class "Default")
      (node (ref "S1") (pin "3") (pinfunction "3_3") (pintype "passive"))
    )
    (net (code "225") (name "unconnected-(U2-NC-Pad40)") (class "Default")
      (node (ref "U2") (pin "40") (pinfunction "NC_40") (pintype "passive"))
    )
    (net (code "226") (name "unconnected-(U4A-PWM-Pad44)") (class "Default")
      (node (ref "U4") (pin "44") (pinfunction "PWM_44") (pintype "passive+no_connect"))
    )
    (net (code "227") (name "unconnected-(U4A-SDI-Pad8)") (class "Default")
      (node (ref "U4") (pin "8") (pinfunction "SDI_8") (pintype "passive+no_connect"))
    )
    (net (code "228") (name "unconnected-(U4A-TE-Pad7)") (class "Default")
      (node (ref "U4") (pin "7") (pinfunction "TE_7") (pintype "passive+no_connect"))
    )
    (net (code "229") (name "unconnected-(U4C-DE-Pad40)") (class "Default")
      (node (ref "U4") (pin "40") (pinfunction "DE_40") (pintype "passive+no_connect"))
    )
    (net (code "230") (name "unconnected-(U4C-HSYNC-Pad42)") (class "Default")
      (node (ref "U4") (pin "42") (pinfunction "HSYNC_42") (pintype "passive+no_connect"))
    )
    (net (code "231") (name "unconnected-(U4C-PCLK-Pad41)") (class "Default")
      (node (ref "U4") (pin "41") (pinfunction "PCLK_41") (pintype "passive+no_connect"))
    )
    (net (code "232") (name "unconnected-(U4C-VSYNC-Pad43)") (class "Default")
      (node (ref "U4") (pin "43") (pinfunction "VSYNC_43") (pintype "passive+no_connect"))
    )
  )
)
